# Test_board_gotta_be_quick.net
KiCad netlist of a schematic drawn in Altium Designer
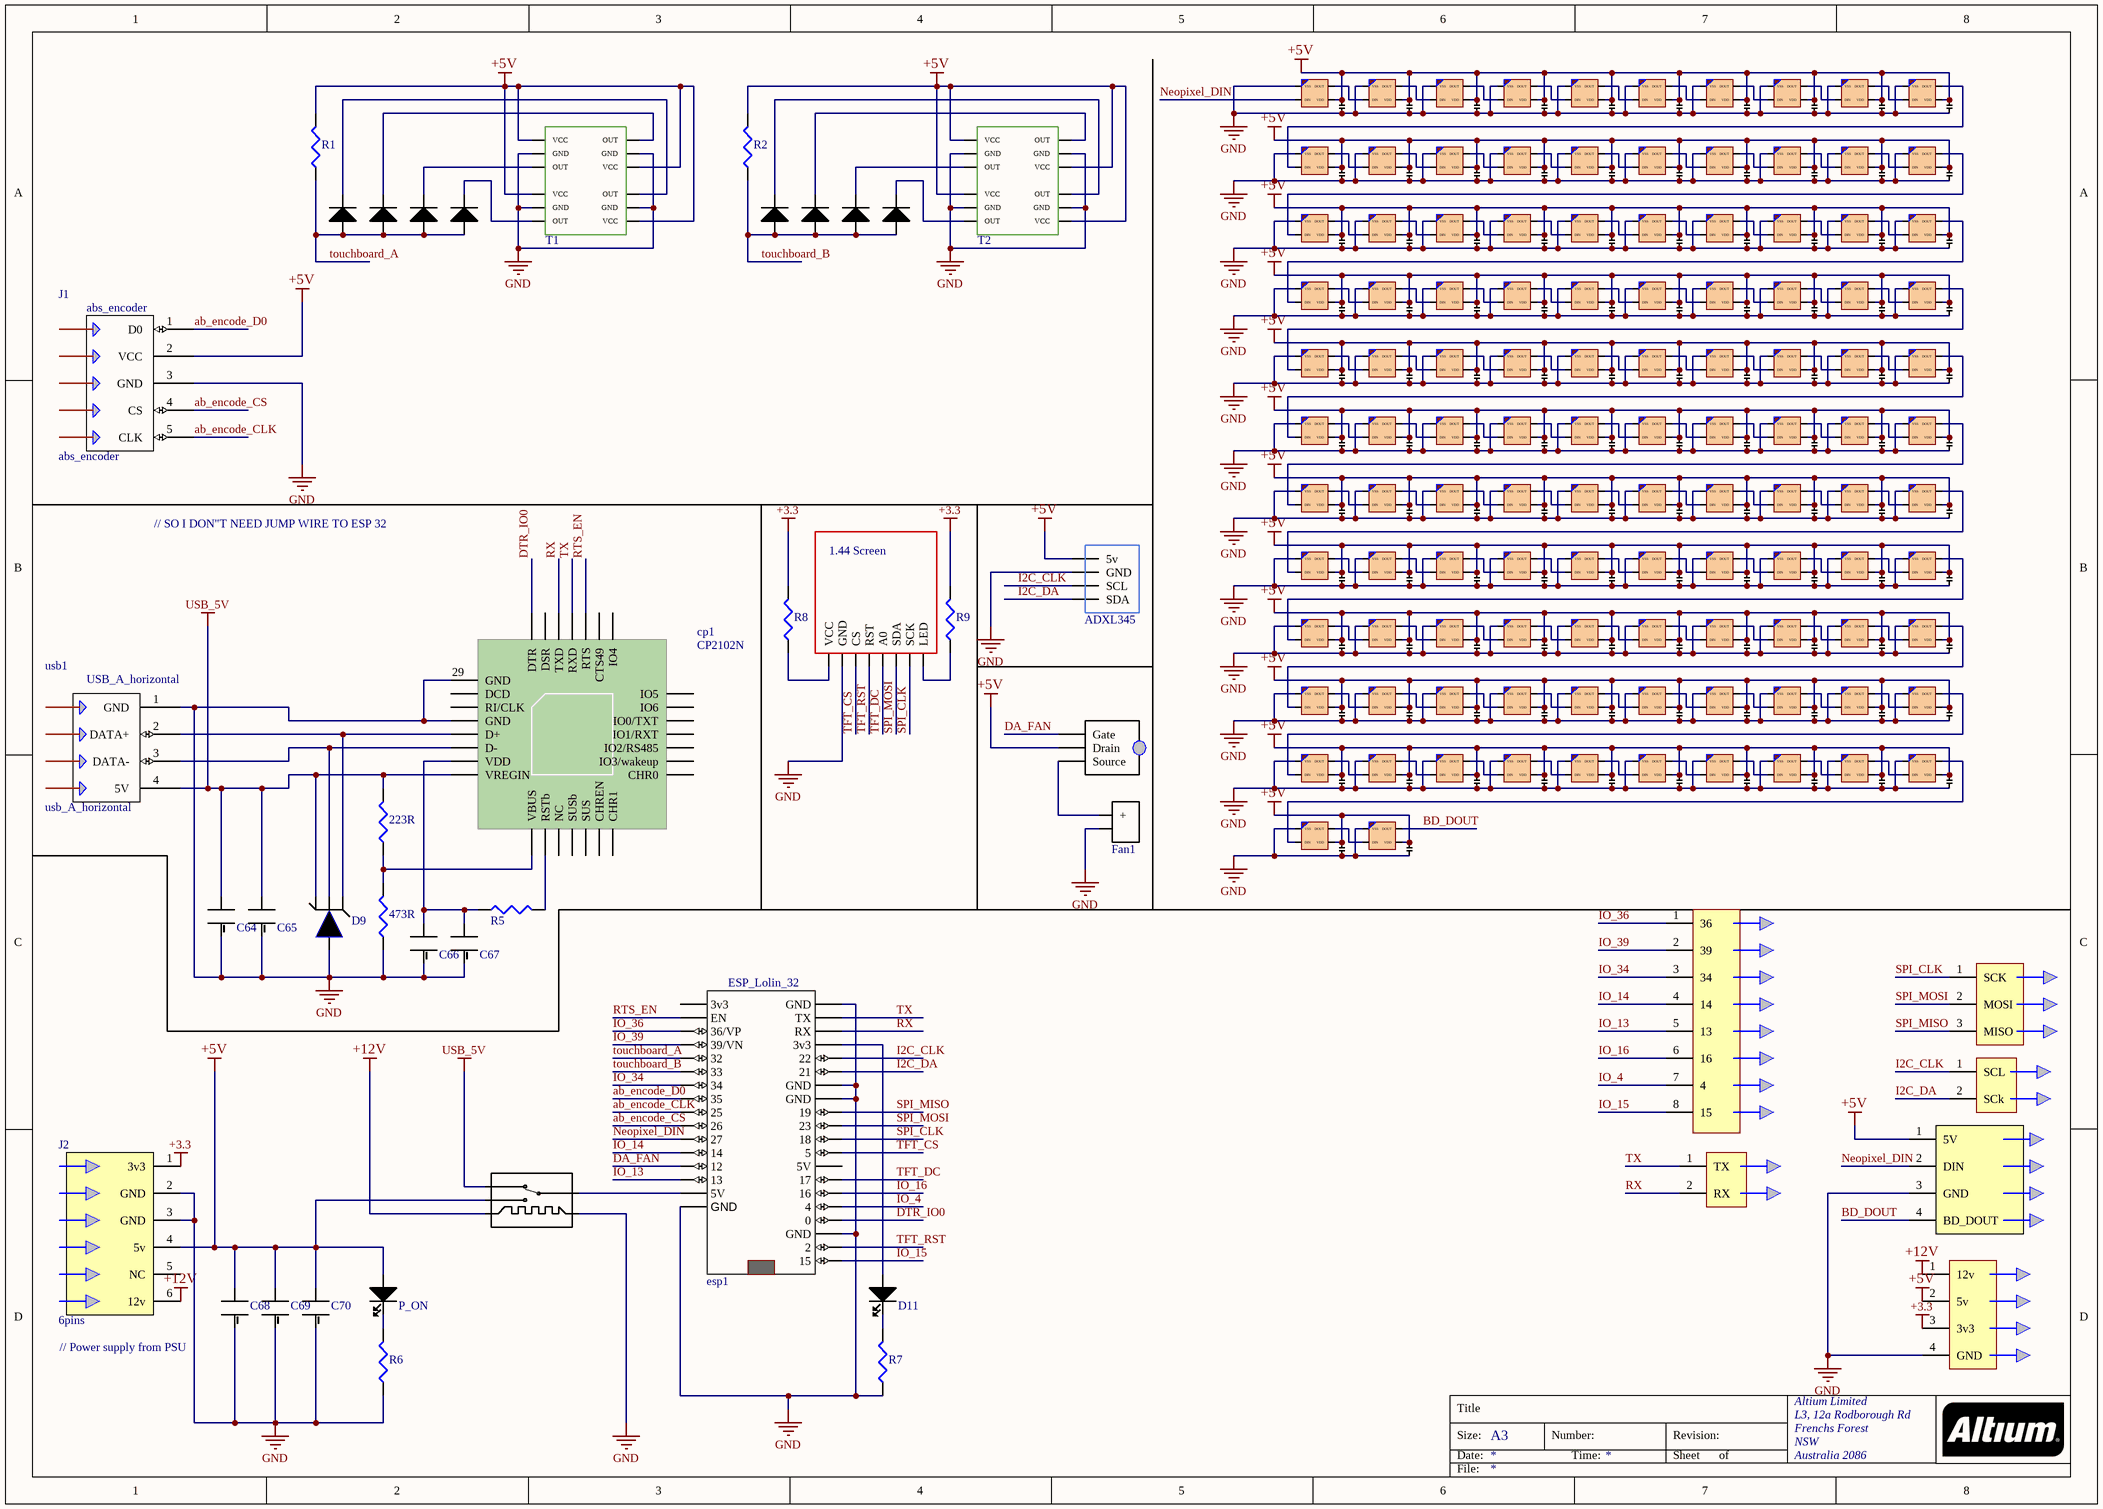
[diagram p0: Test_board_gotta_be_quick.SchDoc]

(export (version "E")
  (design (tool "Eeschema 10.0.6"))
  (components
    (comp (ref "223R")
      (value "22.1k")
      (footprint "R0805")
      (description "Res Thick Film 0805 360 Ohm 1% 0.125W(1/8W) ±100ppm/C Molded SMD Automotive Paper T/R")
      (fields (field (name "TOLERANCE") "1%"))
      (libsource (lib "WTFschlibra") (part "resistor(CRCW0805360RFKEA"))
    )
    (comp (ref "473R")
      (value "47.5k")
      (footprint "R0805")
      (description "Res Thick Film 0805 360 Ohm 1% 0.125W(1/8W) ±100ppm/C Molded SMD Automotive Paper T/R")
      (fields (field (name "TOLERANCE") "1%"))
      (libsource (lib "WTFschlibra") (part "resistor(CRCW0805360RFKEA"))
    )
    (comp (ref "ADXL345")
      (value "ADXL345")
      (footprint "ADXL345")
      (libsource (lib "WTFschlibra") (part "ADXL345"))
    )
    (comp (ref "C1")
      (value "capacitor0.1uf")
      (footprint "Capacitor0805")
      (description "for leds and smol")
      (libsource (lib "WTFschlibra") (part "capacitor0.1uf"))
    )
    (comp (ref "C2")
      (value "capacitor0.1uf")
      (footprint "Capacitor0805")
      (description "for leds and smol")
      (libsource (lib "WTFschlibra") (part "capacitor0.1uf"))
    )
    (comp (ref "C3")
      (value "capacitor0.1uf")
      (footprint "Capacitor0805")
      (description "for leds and smol")
      (libsource (lib "WTFschlibra") (part "capacitor0.1uf"))
    )
    (comp (ref "C4")
      (value "capacitor0.1uf")
      (footprint "Capacitor0805")
      (description "for leds and smol")
      (libsource (lib "WTFschlibra") (part "capacitor0.1uf"))
    )
    (comp (ref "C5")
      (value "capacitor0.1uf")
      (footprint "Capacitor0805")
      (description "for leds and smol")
      (libsource (lib "WTFschlibra") (part "capacitor0.1uf"))
    )
    (comp (ref "C6")
      (value "capacitor0.1uf")
      (footprint "Capacitor0805")
      (description "for leds and smol")
      (libsource (lib "WTFschlibra") (part "capacitor0.1uf"))
    )
    (comp (ref "C7")
      (value "capacitor0.1uf")
      (footprint "Capacitor0805")
      (description "for leds and smol")
      (libsource (lib "WTFschlibra") (part "capacitor0.1uf"))
    )
    (comp (ref "C8")
      (value "capacitor0.1uf")
      (footprint "Capacitor0805")
      (description "for leds and smol")
      (libsource (lib "WTFschlibra") (part "capacitor0.1uf"))
    )
    (comp (ref "C9")
      (value "capacitor0.1uf")
      (footprint "Capacitor0805")
      (description "for leds and smol")
      (libsource (lib "WTFschlibra") (part "capacitor0.1uf"))
    )
    (comp (ref "C10")
      (value "capacitor0.1uf")
      (footprint "Capacitor0805")
      (description "for leds and smol")
      (libsource (lib "WTFschlibra") (part "capacitor0.1uf"))
    )
    (comp (ref "C11")
      (value "capacitor0.1uf")
      (footprint "Capacitor0805")
      (description "for leds and smol")
      (libsource (lib "WTFschlibra") (part "capacitor0.1uf"))
    )
    (comp (ref "C12")
      (value "capacitor0.1uf")
      (footprint "Capacitor0805")
      (description "for leds and smol")
      (libsource (lib "WTFschlibra") (part "capacitor0.1uf"))
    )
    (comp (ref "C13")
      (value "capacitor0.1uf")
      (footprint "Capacitor0805")
      (description "for leds and smol")
      (libsource (lib "WTFschlibra") (part "capacitor0.1uf"))
    )
    (comp (ref "C14")
      (value "capacitor0.1uf")
      (footprint "Capacitor0805")
      (description "for leds and smol")
      (libsource (lib "WTFschlibra") (part "capacitor0.1uf"))
    )
    (comp (ref "C15")
      (value "capacitor0.1uf")
      (footprint "Capacitor0805")
      (description "for leds and smol")
      (libsource (lib "WTFschlibra") (part "capacitor0.1uf"))
    )
    (comp (ref "C16")
      (value "capacitor0.1uf")
      (footprint "Capacitor0805")
      (description "for leds and smol")
      (libsource (lib "WTFschlibra") (part "capacitor0.1uf"))
    )
    (comp (ref "C17")
      (value "capacitor0.1uf")
      (footprint "Capacitor0805")
      (description "for leds and smol")
      (libsource (lib "WTFschlibra") (part "capacitor0.1uf"))
    )
    (comp (ref "C18")
      (value "capacitor0.1uf")
      (footprint "Capacitor0805")
      (description "for leds and smol")
      (libsource (lib "WTFschlibra") (part "capacitor0.1uf"))
    )
    (comp (ref "C19")
      (value "capacitor0.1uf")
      (footprint "Capacitor0805")
      (description "for leds and smol")
      (libsource (lib "WTFschlibra") (part "capacitor0.1uf"))
    )
    (comp (ref "C20")
      (value "capacitor0.1uf")
      (footprint "Capacitor0805")
      (description "for leds and smol")
      (libsource (lib "WTFschlibra") (part "capacitor0.1uf"))
    )
    (comp (ref "C21")
      (value "capacitor0.1uf")
      (footprint "Capacitor0805")
      (description "for leds and smol")
      (libsource (lib "WTFschlibra") (part "capacitor0.1uf"))
    )
    (comp (ref "C22")
      (value "capacitor0.1uf")
      (footprint "Capacitor0805")
      (description "for leds and smol")
      (libsource (lib "WTFschlibra") (part "capacitor0.1uf"))
    )
    (comp (ref "C23")
      (value "capacitor0.1uf")
      (footprint "Capacitor0805")
      (description "for leds and smol")
      (libsource (lib "WTFschlibra") (part "capacitor0.1uf"))
    )
    (comp (ref "C24")
      (value "capacitor0.1uf")
      (footprint "Capacitor0805")
      (description "for leds and smol")
      (libsource (lib "WTFschlibra") (part "capacitor0.1uf"))
    )
    (comp (ref "C25")
      (value "capacitor0.1uf")
      (footprint "Capacitor0805")
      (description "for leds and smol")
      (libsource (lib "WTFschlibra") (part "capacitor0.1uf"))
    )
    (comp (ref "C26")
      (value "capacitor0.1uf")
      (footprint "Capacitor0805")
      (description "for leds and smol")
      (libsource (lib "WTFschlibra") (part "capacitor0.1uf"))
    )
    (comp (ref "C27")
      (value "capacitor0.1uf")
      (footprint "Capacitor0805")
      (description "for leds and smol")
      (libsource (lib "WTFschlibra") (part "capacitor0.1uf"))
    )
    (comp (ref "C28")
      (value "capacitor0.1uf")
      (footprint "Capacitor0805")
      (description "for leds and smol")
      (libsource (lib "WTFschlibra") (part "capacitor0.1uf"))
    )
    (comp (ref "C29")
      (value "capacitor0.1uf")
      (footprint "Capacitor0805")
      (description "for leds and smol")
      (libsource (lib "WTFschlibra") (part "capacitor0.1uf"))
    )
    (comp (ref "C30")
      (value "capacitor0.1uf")
      (footprint "Capacitor0805")
      (description "for leds and smol")
      (libsource (lib "WTFschlibra") (part "capacitor0.1uf"))
    )
    (comp (ref "C31")
      (value "capacitor0.1uf")
      (footprint "Capacitor0805")
      (description "for leds and smol")
      (libsource (lib "WTFschlibra") (part "capacitor0.1uf"))
    )
    (comp (ref "C32")
      (value "capacitor0.1uf")
      (footprint "Capacitor0805")
      (description "for leds and smol")
      (libsource (lib "WTFschlibra") (part "capacitor0.1uf"))
    )
    (comp (ref "C33")
      (value "capacitor0.1uf")
      (footprint "Capacitor0805")
      (description "for leds and smol")
      (libsource (lib "WTFschlibra") (part "capacitor0.1uf"))
    )
    (comp (ref "C34")
      (value "capacitor0.1uf")
      (footprint "Capacitor0805")
      (description "for leds and smol")
      (libsource (lib "WTFschlibra") (part "capacitor0.1uf"))
    )
    (comp (ref "C35")
      (value "capacitor0.1uf")
      (footprint "Capacitor0805")
      (description "for leds and smol")
      (libsource (lib "WTFschlibra") (part "capacitor0.1uf"))
    )
    (comp (ref "C36")
      (value "capacitor0.1uf")
      (footprint "Capacitor0805")
      (description "for leds and smol")
      (libsource (lib "WTFschlibra") (part "capacitor0.1uf"))
    )
    (comp (ref "C37")
      (value "capacitor0.1uf")
      (footprint "Capacitor0805")
      (description "for leds and smol")
      (libsource (lib "WTFschlibra") (part "capacitor0.1uf"))
    )
    (comp (ref "C38")
      (value "capacitor0.1uf")
      (footprint "Capacitor0805")
      (description "for leds and smol")
      (libsource (lib "WTFschlibra") (part "capacitor0.1uf"))
    )
    (comp (ref "C39")
      (value "capacitor0.1uf")
      (footprint "Capacitor0805")
      (description "for leds and smol")
      (libsource (lib "WTFschlibra") (part "capacitor0.1uf"))
    )
    (comp (ref "C40")
      (value "capacitor0.1uf")
      (footprint "Capacitor0805")
      (description "for leds and smol")
      (libsource (lib "WTFschlibra") (part "capacitor0.1uf"))
    )
    (comp (ref "C41")
      (value "capacitor0.1uf")
      (footprint "Capacitor0805")
      (description "for leds and smol")
      (libsource (lib "WTFschlibra") (part "capacitor0.1uf"))
    )
    (comp (ref "C42")
      (value "capacitor0.1uf")
      (footprint "Capacitor0805")
      (description "for leds and smol")
      (libsource (lib "WTFschlibra") (part "capacitor0.1uf"))
    )
    (comp (ref "C43")
      (value "capacitor0.1uf")
      (footprint "Capacitor0805")
      (description "for leds and smol")
      (libsource (lib "WTFschlibra") (part "capacitor0.1uf"))
    )
    (comp (ref "C44")
      (value "capacitor0.1uf")
      (footprint "Capacitor0805")
      (description "for leds and smol")
      (libsource (lib "WTFschlibra") (part "capacitor0.1uf"))
    )
    (comp (ref "C45")
      (value "capacitor0.1uf")
      (footprint "Capacitor0805")
      (description "for leds and smol")
      (libsource (lib "WTFschlibra") (part "capacitor0.1uf"))
    )
    (comp (ref "C46")
      (value "capacitor0.1uf")
      (footprint "Capacitor0805")
      (description "for leds and smol")
      (libsource (lib "WTFschlibra") (part "capacitor0.1uf"))
    )
    (comp (ref "C47")
      (value "capacitor0.1uf")
      (footprint "Capacitor0805")
      (description "for leds and smol")
      (libsource (lib "WTFschlibra") (part "capacitor0.1uf"))
    )
    (comp (ref "C48")
      (value "capacitor0.1uf")
      (footprint "Capacitor0805")
      (description "for leds and smol")
      (libsource (lib "WTFschlibra") (part "capacitor0.1uf"))
    )
    (comp (ref "C49")
      (value "capacitor0.1uf")
      (footprint "Capacitor0805")
      (description "for leds and smol")
      (libsource (lib "WTFschlibra") (part "capacitor0.1uf"))
    )
    (comp (ref "C50")
      (value "capacitor0.1uf")
      (footprint "Capacitor0805")
      (description "for leds and smol")
      (libsource (lib "WTFschlibra") (part "capacitor0.1uf"))
    )
    (comp (ref "C51")
      (value "capacitor0.1uf")
      (footprint "Capacitor0805")
      (description "for leds and smol")
      (libsource (lib "WTFschlibra") (part "capacitor0.1uf"))
    )
    (comp (ref "C52")
      (value "capacitor0.1uf")
      (footprint "Capacitor0805")
      (description "for leds and smol")
      (libsource (lib "WTFschlibra") (part "capacitor0.1uf"))
    )
    (comp (ref "C53")
      (value "capacitor0.1uf")
      (footprint "Capacitor0805")
      (description "for leds and smol")
      (libsource (lib "WTFschlibra") (part "capacitor0.1uf"))
    )
    (comp (ref "C54")
      (value "capacitor0.1uf")
      (footprint "Capacitor0805")
      (description "for leds and smol")
      (libsource (lib "WTFschlibra") (part "capacitor0.1uf"))
    )
    (comp (ref "C55")
      (value "capacitor0.1uf")
      (footprint "Capacitor0805")
      (description "for leds and smol")
      (libsource (lib "WTFschlibra") (part "capacitor0.1uf"))
    )
    (comp (ref "C56")
      (value "capacitor0.1uf")
      (footprint "Capacitor0805")
      (description "for leds and smol")
      (libsource (lib "WTFschlibra") (part "capacitor0.1uf"))
    )
    (comp (ref "C57")
      (value "capacitor0.1uf")
      (footprint "Capacitor0805")
      (description "for leds and smol")
      (libsource (lib "WTFschlibra") (part "capacitor0.1uf"))
    )
    (comp (ref "C58")
      (value "capacitor0.1uf")
      (footprint "Capacitor0805")
      (description "for leds and smol")
      (libsource (lib "WTFschlibra") (part "capacitor0.1uf"))
    )
    (comp (ref "C59")
      (value "capacitor0.1uf")
      (footprint "Capacitor0805")
      (description "for leds and smol")
      (libsource (lib "WTFschlibra") (part "capacitor0.1uf"))
    )
    (comp (ref "C60")
      (value "capacitor0.1uf")
      (footprint "Capacitor0805")
      (description "for leds and smol")
      (libsource (lib "WTFschlibra") (part "capacitor0.1uf"))
    )
    (comp (ref "C61")
      (value "capacitor0.1uf")
      (footprint "Capacitor0805")
      (description "for leds and smol")
      (libsource (lib "WTFschlibra") (part "capacitor0.1uf"))
    )
    (comp (ref "C62")
      (value "capacitor0.1uf")
      (footprint "Capacitor0805")
      (description "for leds and smol")
      (libsource (lib "WTFschlibra") (part "capacitor0.1uf"))
    )
    (comp (ref "C63")
      (value "capacitor0.1uf")
      (footprint "Capacitor0805")
      (description "for leds and smol")
      (libsource (lib "WTFschlibra") (part "capacitor0.1uf"))
    )
    (comp (ref "C64")
      (value "4R7")
      (footprint "Capacitor0603")
      (description "Cap Ceramic 4.7uF 6.3V X5R 20% Pad SMD 0402 85C T/R")
      (fields (field (name "TOLERANCE") "20%"))
      (libsource (lib "WTFschlibra") (part "capacitor0603"))
    )
    (comp (ref "C65")
      (value "104")
      (footprint "Capacitor0603")
      (description "0.1uf")
      (fields (field (name "TOLERANCE") "20%"))
      (libsource (lib "WTFschlibra") (part "capacitor0603"))
    )
    (comp (ref "C66")
      (value "104")
      (footprint "Capacitor0603")
      (description "4.7")
      (fields (field (name "TOLERANCE") "20%"))
      (libsource (lib "WTFschlibra") (part "capacitor0603"))
    )
    (comp (ref "C67")
      (value "4R7")
      (footprint "Capacitor0603")
      (description "0.1")
      (fields (field (name "TOLERANCE") "20%"))
      (libsource (lib "WTFschlibra") (part "capacitor0603"))
    )
    (comp (ref "C68")
      (value "EEU-FM0J331")
      (footprint "2.5mmCapacitor")
      (description "Cap 330 uF;  Tol 20%;  Vol-Rtg 6.3 VDC;  Radial;  6.3x11.2;  Bulk")
      (fields (field (name "TOLERANCE") "20%") (field (name "VOLTAGE") "6.3V"))
      (libsource (lib "WTFschlibra") (part "EEU-FM0J331"))
    )
    (comp (ref "C69")
      (value "EEU-FM0J331")
      (footprint "2.5mmCapacitor")
      (description "Cap 330 uF;  Tol 20%;  Vol-Rtg 6.3 VDC;  Radial;  6.3x11.2;  Bulk")
      (fields (field (name "TOLERANCE") "20%") (field (name "VOLTAGE") "6.3V"))
      (libsource (lib "WTFschlibra") (part "EEU-FM0J331"))
    )
    (comp (ref "C70")
      (value "EEU-FM0J331")
      (footprint "2.5mmCapacitor")
      (description "Cap 330 uF;  Tol 20%;  Vol-Rtg 6.3 VDC;  Radial;  6.3x11.2;  Bulk")
      (fields (field (name "TOLERANCE") "20%") (field (name "VOLTAGE") "6.3V"))
      (libsource (lib "WTFschlibra") (part "EEU-FM0J331"))
    )
    (comp (ref "C71")
      (value "capacitor0.1uf")
      (footprint "Capacitor0805")
      (description "for leds and smol")
      (libsource (lib "WTFschlibra") (part "capacitor0.1uf"))
    )
    (comp (ref "C72")
      (value "capacitor0.1uf")
      (footprint "Capacitor0805")
      (description "for leds and smol")
      (libsource (lib "WTFschlibra") (part "capacitor0.1uf"))
    )
    (comp (ref "C73")
      (value "capacitor0.1uf")
      (footprint "Capacitor0805")
      (description "for leds and smol")
      (libsource (lib "WTFschlibra") (part "capacitor0.1uf"))
    )
    (comp (ref "C74")
      (value "capacitor0.1uf")
      (footprint "Capacitor0805")
      (description "for leds and smol")
      (libsource (lib "WTFschlibra") (part "capacitor0.1uf"))
    )
    (comp (ref "C75")
      (value "capacitor0.1uf")
      (footprint "Capacitor0805")
      (description "for leds and smol")
      (libsource (lib "WTFschlibra") (part "capacitor0.1uf"))
    )
    (comp (ref "C76")
      (value "capacitor0.1uf")
      (footprint "Capacitor0805")
      (description "for leds and smol")
      (libsource (lib "WTFschlibra") (part "capacitor0.1uf"))
    )
    (comp (ref "C77")
      (value "capacitor0.1uf")
      (footprint "Capacitor0805")
      (description "for leds and smol")
      (libsource (lib "WTFschlibra") (part "capacitor0.1uf"))
    )
    (comp (ref "C78")
      (value "capacitor0.1uf")
      (footprint "Capacitor0805")
      (description "for leds and smol")
      (libsource (lib "WTFschlibra") (part "capacitor0.1uf"))
    )
    (comp (ref "C79")
      (value "capacitor0.1uf")
      (footprint "Capacitor0805")
      (description "for leds and smol")
      (libsource (lib "WTFschlibra") (part "capacitor0.1uf"))
    )
    (comp (ref "C80")
      (value "capacitor0.1uf")
      (footprint "Capacitor0805")
      (description "for leds and smol")
      (libsource (lib "WTFschlibra") (part "capacitor0.1uf"))
    )
    (comp (ref "C81")
      (value "capacitor0.1uf")
      (footprint "Capacitor0805")
      (description "for leds and smol")
      (libsource (lib "WTFschlibra") (part "capacitor0.1uf"))
    )
    (comp (ref "C82")
      (value "capacitor0.1uf")
      (footprint "Capacitor0805")
      (description "for leds and smol")
      (libsource (lib "WTFschlibra") (part "capacitor0.1uf"))
    )
    (comp (ref "C83")
      (value "capacitor0.1uf")
      (footprint "Capacitor0805")
      (description "for leds and smol")
      (libsource (lib "WTFschlibra") (part "capacitor0.1uf"))
    )
    (comp (ref "C84")
      (value "capacitor0.1uf")
      (footprint "Capacitor0805")
      (description "for leds and smol")
      (libsource (lib "WTFschlibra") (part "capacitor0.1uf"))
    )
    (comp (ref "C85")
      (value "capacitor0.1uf")
      (footprint "Capacitor0805")
      (description "for leds and smol")
      (libsource (lib "WTFschlibra") (part "capacitor0.1uf"))
    )
    (comp (ref "C86")
      (value "capacitor0.1uf")
      (footprint "Capacitor0805")
      (description "for leds and smol")
      (libsource (lib "WTFschlibra") (part "capacitor0.1uf"))
    )
    (comp (ref "C87")
      (value "capacitor0.1uf")
      (footprint "Capacitor0805")
      (description "for leds and smol")
      (libsource (lib "WTFschlibra") (part "capacitor0.1uf"))
    )
    (comp (ref "C88")
      (value "capacitor0.1uf")
      (footprint "Capacitor0805")
      (description "for leds and smol")
      (libsource (lib "WTFschlibra") (part "capacitor0.1uf"))
    )
    (comp (ref "C89")
      (value "capacitor0.1uf")
      (footprint "Capacitor0805")
      (description "for leds and smol")
      (libsource (lib "WTFschlibra") (part "capacitor0.1uf"))
    )
    (comp (ref "C90")
      (value "capacitor0.1uf")
      (footprint "Capacitor0805")
      (description "for leds and smol")
      (libsource (lib "WTFschlibra") (part "capacitor0.1uf"))
    )
    (comp (ref "C91")
      (value "capacitor0.1uf")
      (footprint "Capacitor0805")
      (description "for leds and smol")
      (libsource (lib "WTFschlibra") (part "capacitor0.1uf"))
    )
    (comp (ref "C92")
      (value "capacitor0.1uf")
      (footprint "Capacitor0805")
      (description "for leds and smol")
      (libsource (lib "WTFschlibra") (part "capacitor0.1uf"))
    )
    (comp (ref "C93")
      (value "capacitor0.1uf")
      (footprint "Capacitor0805")
      (description "for leds and smol")
      (libsource (lib "WTFschlibra") (part "capacitor0.1uf"))
    )
    (comp (ref "C94")
      (value "capacitor0.1uf")
      (footprint "Capacitor0805")
      (description "for leds and smol")
      (libsource (lib "WTFschlibra") (part "capacitor0.1uf"))
    )
    (comp (ref "C95")
      (value "capacitor0.1uf")
      (footprint "Capacitor0805")
      (description "for leds and smol")
      (libsource (lib "WTFschlibra") (part "capacitor0.1uf"))
    )
    (comp (ref "C96")
      (value "capacitor0.1uf")
      (footprint "Capacitor0805")
      (description "for leds and smol")
      (libsource (lib "WTFschlibra") (part "capacitor0.1uf"))
    )
    (comp (ref "C97")
      (value "capacitor0.1uf")
      (footprint "Capacitor0805")
      (description "for leds and smol")
      (libsource (lib "WTFschlibra") (part "capacitor0.1uf"))
    )
    (comp (ref "C98")
      (value "capacitor0.1uf")
      (footprint "Capacitor0805")
      (description "for leds and smol")
      (libsource (lib "WTFschlibra") (part "capacitor0.1uf"))
    )
    (comp (ref "C99")
      (value "capacitor0.1uf")
      (footprint "Capacitor0805")
      (description "for leds and smol")
      (libsource (lib "WTFschlibra") (part "capacitor0.1uf"))
    )
    (comp (ref "C100")
      (value "capacitor0.1uf")
      (footprint "Capacitor0805")
      (description "for leds and smol")
      (libsource (lib "WTFschlibra") (part "capacitor0.1uf"))
    )
    (comp (ref "C101")
      (value "capacitor0.1uf")
      (footprint "Capacitor0805")
      (description "for leds and smol")
      (libsource (lib "WTFschlibra") (part "capacitor0.1uf"))
    )
    (comp (ref "C102")
      (value "capacitor0.1uf")
      (footprint "Capacitor0805")
      (description "for leds and smol")
      (libsource (lib "WTFschlibra") (part "capacitor0.1uf"))
    )
    (comp (ref "C103")
      (value "capacitor0.1uf")
      (footprint "Capacitor0805")
      (description "for leds and smol")
      (libsource (lib "WTFschlibra") (part "capacitor0.1uf"))
    )
    (comp (ref "C104")
      (value "capacitor0.1uf")
      (footprint "Capacitor0805")
      (description "for leds and smol")
      (libsource (lib "WTFschlibra") (part "capacitor0.1uf"))
    )
    (comp (ref "C105")
      (value "capacitor0.1uf")
      (footprint "Capacitor0805")
      (description "for leds and smol")
      (libsource (lib "WTFschlibra") (part "capacitor0.1uf"))
    )
    (comp (ref "C106")
      (value "capacitor0.1uf")
      (footprint "Capacitor0805")
      (description "for leds and smol")
      (libsource (lib "WTFschlibra") (part "capacitor0.1uf"))
    )
    (comp (ref "C107")
      (value "capacitor0.1uf")
      (footprint "Capacitor0805")
      (description "for leds and smol")
      (libsource (lib "WTFschlibra") (part "capacitor0.1uf"))
    )
    (comp (ref "C108")
      (value "capacitor0.1uf")
      (footprint "Capacitor0805")
      (description "for leds and smol")
      (libsource (lib "WTFschlibra") (part "capacitor0.1uf"))
    )
    (comp (ref "C109")
      (value "capacitor0.1uf")
      (footprint "Capacitor0805")
      (description "for leds and smol")
      (libsource (lib "WTFschlibra") (part "capacitor0.1uf"))
    )
    (comp (ref "C110")
      (value "capacitor0.1uf")
      (footprint "Capacitor0805")
      (description "for leds and smol")
      (libsource (lib "WTFschlibra") (part "capacitor0.1uf"))
    )
    (comp (ref "C111")
      (value "capacitor0.1uf")
      (footprint "Capacitor0805")
      (description "for leds and smol")
      (libsource (lib "WTFschlibra") (part "capacitor0.1uf"))
    )
    (comp (ref "C112")
      (value "capacitor0.1uf")
      (footprint "Capacitor0805")
      (description "for leds and smol")
      (libsource (lib "WTFschlibra") (part "capacitor0.1uf"))
    )
    (comp (ref "C113")
      (value "capacitor0.1uf")
      (footprint "Capacitor0805")
      (description "for leds and smol")
      (libsource (lib "WTFschlibra") (part "capacitor0.1uf"))
    )
    (comp (ref "C114")
      (value "capacitor0.1uf")
      (footprint "Capacitor0805")
      (description "for leds and smol")
      (libsource (lib "WTFschlibra") (part "capacitor0.1uf"))
    )
    (comp (ref "C115")
      (value "capacitor0.1uf")
      (footprint "Capacitor0805")
      (description "for leds and smol")
      (libsource (lib "WTFschlibra") (part "capacitor0.1uf"))
    )
    (comp (ref "C116")
      (value "capacitor0.1uf")
      (footprint "Capacitor0805")
      (description "for leds and smol")
      (libsource (lib "WTFschlibra") (part "capacitor0.1uf"))
    )
    (comp (ref "C117")
      (value "capacitor0.1uf")
      (footprint "Capacitor0805")
      (description "for leds and smol")
      (libsource (lib "WTFschlibra") (part "capacitor0.1uf"))
    )
    (comp (ref "C118")
      (value "capacitor0.1uf")
      (footprint "Capacitor0805")
      (description "for leds and smol")
      (libsource (lib "WTFschlibra") (part "capacitor0.1uf"))
    )
    (comp (ref "C119")
      (value "capacitor0.1uf")
      (footprint "Capacitor0805")
      (description "for leds and smol")
      (libsource (lib "WTFschlibra") (part "capacitor0.1uf"))
    )
    (comp (ref "cp1")
      (value "CP2102N")
      (footprint "CP2102N_QFN28")
      (description "Full Speed USB to UART Bridge USB 2.0 3.3V T/R Automotive 28-Pin QFN EP")
      (libsource (lib "WTFschlibra") (part "CP2102N-A02-GQFN28R"))
    )
    (comp (ref "D1")
      (value "LL4148")
      (footprint "SOD80-LL4148")
      (description "ON SEMICONDUCTOR - LL4148 - Small Signal Diode, Single, 100 V, 200 mA, 1 V, 4 ns, 2 A")
      (fields (field (name "VOLTAGE") "100V"))
      (libsource (lib "WTFschlibra") (part "LL4148"))
    )
    (comp (ref "D2")
      (value "LL4148")
      (footprint "SOD80-LL4148")
      (description "ON SEMICONDUCTOR - LL4148 - Small Signal Diode, Single, 100 V, 200 mA, 1 V, 4 ns, 2 A")
      (fields (field (name "VOLTAGE") "100V"))
      (libsource (lib "WTFschlibra") (part "LL4148"))
    )
    (comp (ref "D3")
      (value "LL4148")
      (footprint "SOD80-LL4148")
      (description "ON SEMICONDUCTOR - LL4148 - Small Signal Diode, Single, 100 V, 200 mA, 1 V, 4 ns, 2 A")
      (fields (field (name "VOLTAGE") "100V"))
      (libsource (lib "WTFschlibra") (part "LL4148"))
    )
    (comp (ref "D4")
      (value "LL4148")
      (footprint "SOD80-LL4148")
      (description "ON SEMICONDUCTOR - LL4148 - Small Signal Diode, Single, 100 V, 200 mA, 1 V, 4 ns, 2 A")
      (fields (field (name "VOLTAGE") "100V"))
      (libsource (lib "WTFschlibra") (part "LL4148"))
    )
    (comp (ref "D5")
      (value "LL4148")
      (footprint "SOD80-LL4148")
      (description "ON SEMICONDUCTOR - LL4148 - Small Signal Diode, Single, 100 V, 200 mA, 1 V, 4 ns, 2 A")
      (fields (field (name "VOLTAGE") "100V"))
      (libsource (lib "WTFschlibra") (part "LL4148"))
    )
    (comp (ref "D6")
      (value "LL4148")
      (footprint "SOD80-LL4148")
      (description "ON SEMICONDUCTOR - LL4148 - Small Signal Diode, Single, 100 V, 200 mA, 1 V, 4 ns, 2 A")
      (fields (field (name "VOLTAGE") "100V"))
      (libsource (lib "WTFschlibra") (part "LL4148"))
    )
    (comp (ref "D7")
      (value "LL4148")
      (footprint "SOD80-LL4148")
      (description "ON SEMICONDUCTOR - LL4148 - Small Signal Diode, Single, 100 V, 200 mA, 1 V, 4 ns, 2 A")
      (fields (field (name "VOLTAGE") "100V"))
      (libsource (lib "WTFschlibra") (part "LL4148"))
    )
    (comp (ref "D8")
      (value "LL4148")
      (footprint "SOD80-LL4148")
      (description "ON SEMICONDUCTOR - LL4148 - Small Signal Diode, Single, 100 V, 200 mA, 1 V, 4 ns, 2 A")
      (fields (field (name "VOLTAGE") "100V"))
      (libsource (lib "WTFschlibra") (part "LL4148"))
    )
    (comp (ref "D9")
      (value "SP0503BAHTG")
      (footprint "SP0503BAHTG - SOT143-4")
      (description "ESD Suppressor TVS 5.5V 4-Pin(3+Tab) SOT-143 T/R")
      (libsource (lib "WTFschlibra") (part "SP0503BAHTG"))
    )
    (comp (ref "D11")
      (value "esp_on")
      (footprint "LED0603")
      (description "LED BLUE CLEAR CHIP SMD")
      (libsource (lib "WTFschlibra") (part "LTST-C190TBKT"))
    )
    (comp (ref "esp1")
      (value "processor")
      (footprint "ESP_32_socket")
      (libsource (lib "WTFschlibra") (part "ESP_32_lolin"))
    )
    (comp (ref "Fan1")
      (value "5vFanPin")
      (footprint "1x2 dupont")
      (libsource (lib "WTFschlibra") (part "5vFanPin"))
    )
    (comp (ref "irl") (value "IRL3713") (footprint "TO_220") (libsource (lib "WTFschlibra") (part "IRL3713")))
    (comp (ref "J1")
      (value "abs_encoder")
      (footprint "xh 2.54 5 pin")
      (libsource (lib "WTFschlibra") (part "Abs_encoder_pins"))
    )
    (comp (ref "J2")
      (value "6pins")
      (footprint "4.2mm 6pin power connector")
      (description "MiniFit Jr RA Hdr Assy LCP 6 w/press pgs")
      (libsource (lib "WTFschlibra") (part "4.2mm 6pin module connector"))
    )
    (comp (ref "J3")
      (value "ws2812")
      (footprint "1x4 DUPONT")
      (description "for neopixels array")
      (libsource (lib "WTFschlibra") (part "4.2mm 4pin 39300040"))
    )
    (comp (ref "J4")
      (value "SPI")
      (footprint "1x3 DUPONT")
      (libsource (lib "WTFschlibra") (part "1x3 dupont SPI"))
    )
    (comp (ref "J5")
      (value "I2C")
      (footprint "1x2 dupont")
      (libsource (lib "WTFschlibra") (part "1x2 dupont I2C"))
    )
    (comp (ref "J6")
      (value "1x8 dupont io pins")
      (footprint "1x8 dupont")
      (libsource (lib "WTFschlibra") (part "1x8 dupont io pins"))
    )
    (comp (ref "J7")
      (value "1x4 dupont power")
      (footprint "1x4 DUPONT")
      (libsource (lib "WTFschlibra") (part "1x4 dupont power"))
    )
    (comp (ref "J8")
      (value "TX")
      (footprint "1x2 dupont")
      (libsource (lib "WTFschlibra") (part "1x2 dupont TXRX"))
    )
    (comp (ref "LED1")
      (value "Ws2812B")
      (footprint "ws2812b")
      (libsource (lib "WTFschlibra") (part "Ws2812B"))
    )
    (comp (ref "LED2")
      (value "Ws2812B")
      (footprint "ws2812b")
      (libsource (lib "WTFschlibra") (part "Ws2812B"))
    )
    (comp (ref "LED3")
      (value "Ws2812B")
      (footprint "ws2812b")
      (libsource (lib "WTFschlibra") (part "Ws2812B"))
    )
    (comp (ref "LED4")
      (value "Ws2812B")
      (footprint "ws2812b")
      (libsource (lib "WTFschlibra") (part "Ws2812B"))
    )
    (comp (ref "LED5")
      (value "Ws2812B")
      (footprint "ws2812b")
      (libsource (lib "WTFschlibra") (part "Ws2812B"))
    )
    (comp (ref "LED6")
      (value "Ws2812B")
      (footprint "ws2812b")
      (libsource (lib "WTFschlibra") (part "Ws2812B"))
    )
    (comp (ref "LED7")
      (value "Ws2812B")
      (footprint "ws2812b")
      (libsource (lib "WTFschlibra") (part "Ws2812B"))
    )
    (comp (ref "LED8")
      (value "Ws2812B")
      (footprint "ws2812b")
      (libsource (lib "WTFschlibra") (part "Ws2812B"))
    )
    (comp (ref "LED9")
      (value "Ws2812B")
      (footprint "ws2812b")
      (libsource (lib "WTFschlibra") (part "Ws2812B"))
    )
    (comp (ref "LED10")
      (value "Ws2812B")
      (footprint "ws2812b")
      (libsource (lib "WTFschlibra") (part "Ws2812B"))
    )
    (comp (ref "LED11")
      (value "Ws2812B")
      (footprint "ws2812b")
      (libsource (lib "WTFschlibra") (part "Ws2812B"))
    )
    (comp (ref "LED12")
      (value "Ws2812B")
      (footprint "ws2812b")
      (libsource (lib "WTFschlibra") (part "Ws2812B"))
    )
    (comp (ref "LED13")
      (value "Ws2812B")
      (footprint "ws2812b")
      (libsource (lib "WTFschlibra") (part "Ws2812B"))
    )
    (comp (ref "LED14")
      (value "Ws2812B")
      (footprint "ws2812b")
      (libsource (lib "WTFschlibra") (part "Ws2812B"))
    )
    (comp (ref "LED15")
      (value "Ws2812B")
      (footprint "ws2812b")
      (libsource (lib "WTFschlibra") (part "Ws2812B"))
    )
    (comp (ref "LED16")
      (value "Ws2812B")
      (footprint "ws2812b")
      (libsource (lib "WTFschlibra") (part "Ws2812B"))
    )
    (comp (ref "LED17")
      (value "Ws2812B")
      (footprint "ws2812b")
      (libsource (lib "WTFschlibra") (part "Ws2812B"))
    )
    (comp (ref "LED18")
      (value "Ws2812B")
      (footprint "ws2812b")
      (libsource (lib "WTFschlibra") (part "Ws2812B"))
    )
    (comp (ref "LED19")
      (value "Ws2812B")
      (footprint "ws2812b")
      (libsource (lib "WTFschlibra") (part "Ws2812B"))
    )
    (comp (ref "LED20")
      (value "Ws2812B")
      (footprint "ws2812b")
      (libsource (lib "WTFschlibra") (part "Ws2812B"))
    )
    (comp (ref "LED21")
      (value "Ws2812B")
      (footprint "ws2812b")
      (libsource (lib "WTFschlibra") (part "Ws2812B"))
    )
    (comp (ref "LED22")
      (value "Ws2812B")
      (footprint "ws2812b")
      (libsource (lib "WTFschlibra") (part "Ws2812B"))
    )
    (comp (ref "LED23")
      (value "Ws2812B")
      (footprint "ws2812b")
      (libsource (lib "WTFschlibra") (part "Ws2812B"))
    )
    (comp (ref "LED24")
      (value "Ws2812B")
      (footprint "ws2812b")
      (libsource (lib "WTFschlibra") (part "Ws2812B"))
    )
    (comp (ref "LED25")
      (value "Ws2812B")
      (footprint "ws2812b")
      (libsource (lib "WTFschlibra") (part "Ws2812B"))
    )
    (comp (ref "LED26")
      (value "Ws2812B")
      (footprint "ws2812b")
      (libsource (lib "WTFschlibra") (part "Ws2812B"))
    )
    (comp (ref "LED27")
      (value "Ws2812B")
      (footprint "ws2812b")
      (libsource (lib "WTFschlibra") (part "Ws2812B"))
    )
    (comp (ref "LED28")
      (value "Ws2812B")
      (footprint "ws2812b")
      (libsource (lib "WTFschlibra") (part "Ws2812B"))
    )
    (comp (ref "LED29")
      (value "Ws2812B")
      (footprint "ws2812b")
      (libsource (lib "WTFschlibra") (part "Ws2812B"))
    )
    (comp (ref "LED30")
      (value "Ws2812B")
      (footprint "ws2812b")
      (libsource (lib "WTFschlibra") (part "Ws2812B"))
    )
    (comp (ref "LED31")
      (value "Ws2812B")
      (footprint "ws2812b")
      (libsource (lib "WTFschlibra") (part "Ws2812B"))
    )
    (comp (ref "LED32")
      (value "Ws2812B")
      (footprint "ws2812b")
      (libsource (lib "WTFschlibra") (part "Ws2812B"))
    )
    (comp (ref "LED33")
      (value "Ws2812B")
      (footprint "ws2812b")
      (libsource (lib "WTFschlibra") (part "Ws2812B"))
    )
    (comp (ref "LED34")
      (value "Ws2812B")
      (footprint "ws2812b")
      (libsource (lib "WTFschlibra") (part "Ws2812B"))
    )
    (comp (ref "LED35")
      (value "Ws2812B")
      (footprint "ws2812b")
      (libsource (lib "WTFschlibra") (part "Ws2812B"))
    )
    (comp (ref "LED36")
      (value "Ws2812B")
      (footprint "ws2812b")
      (libsource (lib "WTFschlibra") (part "Ws2812B"))
    )
    (comp (ref "LED37")
      (value "Ws2812B")
      (footprint "ws2812b")
      (libsource (lib "WTFschlibra") (part "Ws2812B"))
    )
    (comp (ref "LED38")
      (value "Ws2812B")
      (footprint "ws2812b")
      (libsource (lib "WTFschlibra") (part "Ws2812B"))
    )
    (comp (ref "LED39")
      (value "Ws2812B")
      (footprint "ws2812b")
      (libsource (lib "WTFschlibra") (part "Ws2812B"))
    )
    (comp (ref "LED40")
      (value "Ws2812B")
      (footprint "ws2812b")
      (libsource (lib "WTFschlibra") (part "Ws2812B"))
    )
    (comp (ref "LED41")
      (value "Ws2812B")
      (footprint "ws2812b")
      (libsource (lib "WTFschlibra") (part "Ws2812B"))
    )
    (comp (ref "LED42")
      (value "Ws2812B")
      (footprint "ws2812b")
      (libsource (lib "WTFschlibra") (part "Ws2812B"))
    )
    (comp (ref "LED43")
      (value "Ws2812B")
      (footprint "ws2812b")
      (libsource (lib "WTFschlibra") (part "Ws2812B"))
    )
    (comp (ref "LED44")
      (value "Ws2812B")
      (footprint "ws2812b")
      (libsource (lib "WTFschlibra") (part "Ws2812B"))
    )
    (comp (ref "LED45")
      (value "Ws2812B")
      (footprint "ws2812b")
      (libsource (lib "WTFschlibra") (part "Ws2812B"))
    )
    (comp (ref "LED46")
      (value "Ws2812B")
      (footprint "ws2812b")
      (libsource (lib "WTFschlibra") (part "Ws2812B"))
    )
    (comp (ref "LED47")
      (value "Ws2812B")
      (footprint "ws2812b")
      (libsource (lib "WTFschlibra") (part "Ws2812B"))
    )
    (comp (ref "LED48")
      (value "Ws2812B")
      (footprint "ws2812b")
      (libsource (lib "WTFschlibra") (part "Ws2812B"))
    )
    (comp (ref "LED49")
      (value "Ws2812B")
      (footprint "ws2812b")
      (libsource (lib "WTFschlibra") (part "Ws2812B"))
    )
    (comp (ref "LED50")
      (value "Ws2812B")
      (footprint "ws2812b")
      (libsource (lib "WTFschlibra") (part "Ws2812B"))
    )
    (comp (ref "LED51")
      (value "Ws2812B")
      (footprint "ws2812b")
      (libsource (lib "WTFschlibra") (part "Ws2812B"))
    )
    (comp (ref "LED52")
      (value "Ws2812B")
      (footprint "ws2812b")
      (libsource (lib "WTFschlibra") (part "Ws2812B"))
    )
    (comp (ref "LED53")
      (value "Ws2812B")
      (footprint "ws2812b")
      (libsource (lib "WTFschlibra") (part "Ws2812B"))
    )
    (comp (ref "LED54")
      (value "Ws2812B")
      (footprint "ws2812b")
      (libsource (lib "WTFschlibra") (part "Ws2812B"))
    )
    (comp (ref "LED55")
      (value "Ws2812B")
      (footprint "ws2812b")
      (libsource (lib "WTFschlibra") (part "Ws2812B"))
    )
    (comp (ref "LED56")
      (value "Ws2812B")
      (footprint "ws2812b")
      (libsource (lib "WTFschlibra") (part "Ws2812B"))
    )
    (comp (ref "LED57")
      (value "Ws2812B")
      (footprint "ws2812b")
      (libsource (lib "WTFschlibra") (part "Ws2812B"))
    )
    (comp (ref "LED58")
      (value "Ws2812B")
      (footprint "ws2812b")
      (libsource (lib "WTFschlibra") (part "Ws2812B"))
    )
    (comp (ref "LED59")
      (value "Ws2812B")
      (footprint "ws2812b")
      (libsource (lib "WTFschlibra") (part "Ws2812B"))
    )
    (comp (ref "LED60")
      (value "Ws2812B")
      (footprint "ws2812b")
      (libsource (lib "WTFschlibra") (part "Ws2812B"))
    )
    (comp (ref "LED61")
      (value "Ws2812B")
      (footprint "ws2812b")
      (libsource (lib "WTFschlibra") (part "Ws2812B"))
    )
    (comp (ref "LED62")
      (value "Ws2812B")
      (footprint "ws2812b")
      (libsource (lib "WTFschlibra") (part "Ws2812B"))
    )
    (comp (ref "LED63")
      (value "Ws2812B")
      (footprint "ws2812b")
      (libsource (lib "WTFschlibra") (part "Ws2812B"))
    )
    (comp (ref "LED64")
      (value "Ws2812B")
      (footprint "ws2812b")
      (libsource (lib "WTFschlibra") (part "Ws2812B"))
    )
    (comp (ref "LED65")
      (value "Ws2812B")
      (footprint "ws2812b")
      (libsource (lib "WTFschlibra") (part "Ws2812B"))
    )
    (comp (ref "LED66")
      (value "Ws2812B")
      (footprint "ws2812b")
      (libsource (lib "WTFschlibra") (part "Ws2812B"))
    )
    (comp (ref "LED67")
      (value "Ws2812B")
      (footprint "ws2812b")
      (libsource (lib "WTFschlibra") (part "Ws2812B"))
    )
    (comp (ref "LED68")
      (value "Ws2812B")
      (footprint "ws2812b")
      (libsource (lib "WTFschlibra") (part "Ws2812B"))
    )
    (comp (ref "LED69")
      (value "Ws2812B")
      (footprint "ws2812b")
      (libsource (lib "WTFschlibra") (part "Ws2812B"))
    )
    (comp (ref "LED70")
      (value "Ws2812B")
      (footprint "ws2812b")
      (libsource (lib "WTFschlibra") (part "Ws2812B"))
    )
    (comp (ref "LED71")
      (value "Ws2812B")
      (footprint "ws2812b")
      (libsource (lib "WTFschlibra") (part "Ws2812B"))
    )
    (comp (ref "LED72")
      (value "Ws2812B")
      (footprint "ws2812b")
      (libsource (lib "WTFschlibra") (part "Ws2812B"))
    )
    (comp (ref "LED73")
      (value "Ws2812B")
      (footprint "ws2812b")
      (libsource (lib "WTFschlibra") (part "Ws2812B"))
    )
    (comp (ref "LED74")
      (value "Ws2812B")
      (footprint "ws2812b")
      (libsource (lib "WTFschlibra") (part "Ws2812B"))
    )
    (comp (ref "LED75")
      (value "Ws2812B")
      (footprint "ws2812b")
      (libsource (lib "WTFschlibra") (part "Ws2812B"))
    )
    (comp (ref "LED76")
      (value "Ws2812B")
      (footprint "ws2812b")
      (libsource (lib "WTFschlibra") (part "Ws2812B"))
    )
    (comp (ref "LED77")
      (value "Ws2812B")
      (footprint "ws2812b")
      (libsource (lib "WTFschlibra") (part "Ws2812B"))
    )
    (comp (ref "LED78")
      (value "Ws2812B")
      (footprint "ws2812b")
      (libsource (lib "WTFschlibra") (part "Ws2812B"))
    )
    (comp (ref "LED79")
      (value "Ws2812B")
      (footprint "ws2812b")
      (libsource (lib "WTFschlibra") (part "Ws2812B"))
    )
    (comp (ref "LED80")
      (value "Ws2812B")
      (footprint "ws2812b")
      (libsource (lib "WTFschlibra") (part "Ws2812B"))
    )
    (comp (ref "LED81")
      (value "Ws2812B")
      (footprint "ws2812b")
      (libsource (lib "WTFschlibra") (part "Ws2812B"))
    )
    (comp (ref "LED82")
      (value "Ws2812B")
      (footprint "ws2812b")
      (libsource (lib "WTFschlibra") (part "Ws2812B"))
    )
    (comp (ref "LED83")
      (value "Ws2812B")
      (footprint "ws2812b")
      (libsource (lib "WTFschlibra") (part "Ws2812B"))
    )
    (comp (ref "LED84")
      (value "Ws2812B")
      (footprint "ws2812b")
      (libsource (lib "WTFschlibra") (part "Ws2812B"))
    )
    (comp (ref "LED85")
      (value "Ws2812B")
      (footprint "ws2812b")
      (libsource (lib "WTFschlibra") (part "Ws2812B"))
    )
    (comp (ref "LED86")
      (value "Ws2812B")
      (footprint "ws2812b")
      (libsource (lib "WTFschlibra") (part "Ws2812B"))
    )
    (comp (ref "LED87")
      (value "Ws2812B")
      (footprint "ws2812b")
      (libsource (lib "WTFschlibra") (part "Ws2812B"))
    )
    (comp (ref "LED88")
      (value "Ws2812B")
      (footprint "ws2812b")
      (libsource (lib "WTFschlibra") (part "Ws2812B"))
    )
    (comp (ref "LED89")
      (value "Ws2812B")
      (footprint "ws2812b")
      (libsource (lib "WTFschlibra") (part "Ws2812B"))
    )
    (comp (ref "LED90")
      (value "Ws2812B")
      (footprint "ws2812b")
      (libsource (lib "WTFschlibra") (part "Ws2812B"))
    )
    (comp (ref "LED91")
      (value "Ws2812B")
      (footprint "ws2812b")
      (libsource (lib "WTFschlibra") (part "Ws2812B"))
    )
    (comp (ref "LED92")
      (value "Ws2812B")
      (footprint "ws2812b")
      (libsource (lib "WTFschlibra") (part "Ws2812B"))
    )
    (comp (ref "LED93")
      (value "Ws2812B")
      (footprint "ws2812b")
      (libsource (lib "WTFschlibra") (part "Ws2812B"))
    )
    (comp (ref "LED94")
      (value "Ws2812B")
      (footprint "ws2812b")
      (libsource (lib "WTFschlibra") (part "Ws2812B"))
    )
    (comp (ref "LED95")
      (value "Ws2812B")
      (footprint "ws2812b")
      (libsource (lib "WTFschlibra") (part "Ws2812B"))
    )
    (comp (ref "LED96")
      (value "Ws2812B")
      (footprint "ws2812b")
      (libsource (lib "WTFschlibra") (part "Ws2812B"))
    )
    (comp (ref "LED97")
      (value "Ws2812B")
      (footprint "ws2812b")
      (libsource (lib "WTFschlibra") (part "Ws2812B"))
    )
    (comp (ref "LED98")
      (value "Ws2812B")
      (footprint "ws2812b")
      (libsource (lib "WTFschlibra") (part "Ws2812B"))
    )
    (comp (ref "LED99")
      (value "Ws2812B")
      (footprint "ws2812b")
      (libsource (lib "WTFschlibra") (part "Ws2812B"))
    )
    (comp (ref "LED100")
      (value "Ws2812B")
      (footprint "ws2812b")
      (libsource (lib "WTFschlibra") (part "Ws2812B"))
    )
    (comp (ref "LED101")
      (value "Ws2812B")
      (footprint "ws2812b")
      (libsource (lib "WTFschlibra") (part "Ws2812B"))
    )
    (comp (ref "LED102")
      (value "Ws2812B")
      (footprint "ws2812b")
      (libsource (lib "WTFschlibra") (part "Ws2812B"))
    )
    (comp (ref "LED103")
      (value "Ws2812B")
      (footprint "ws2812b")
      (libsource (lib "WTFschlibra") (part "Ws2812B"))
    )
    (comp (ref "LED104")
      (value "Ws2812B")
      (footprint "ws2812b")
      (libsource (lib "WTFschlibra") (part "Ws2812B"))
    )
    (comp (ref "LED105")
      (value "Ws2812B")
      (footprint "ws2812b")
      (libsource (lib "WTFschlibra") (part "Ws2812B"))
    )
    (comp (ref "LED106")
      (value "Ws2812B")
      (footprint "ws2812b")
      (libsource (lib "WTFschlibra") (part "Ws2812B"))
    )
    (comp (ref "LED107")
      (value "Ws2812B")
      (footprint "ws2812b")
      (libsource (lib "WTFschlibra") (part "Ws2812B"))
    )
    (comp (ref "LED108")
      (value "Ws2812B")
      (footprint "ws2812b")
      (libsource (lib "WTFschlibra") (part "Ws2812B"))
    )
    (comp (ref "LED109")
      (value "Ws2812B")
      (footprint "ws2812b")
      (libsource (lib "WTFschlibra") (part "Ws2812B"))
    )
    (comp (ref "LED110")
      (value "Ws2812B")
      (footprint "ws2812b")
      (libsource (lib "WTFschlibra") (part "Ws2812B"))
    )
    (comp (ref "LED111")
      (value "Ws2812B")
      (footprint "ws2812b")
      (libsource (lib "WTFschlibra") (part "Ws2812B"))
    )
    (comp (ref "LED112")
      (value "Ws2812B")
      (footprint "ws2812b")
      (libsource (lib "WTFschlibra") (part "Ws2812B"))
    )
    (comp (ref "P_ON")
      (value "Led")
      (footprint "LED0603")
      (description "LED BLUE CLEAR CHIP SMD")
      (libsource (lib "WTFschlibra") (part "LTST-C190TBKT"))
    )
    (comp (ref "R1")
      (value "102R")
      (footprint "R0805")
      (description "Res Thick Film 0805 360 Ohm 1% 0.125W(1/8W) ±100ppm/C Molded SMD Automotive Paper T/R")
      (fields (field (name "TOLERANCE") "1%"))
      (libsource (lib "WTFschlibra") (part "resistor(CRCW0805360RFKEA"))
    )
    (comp (ref "R2")
      (value "102R")
      (footprint "R0805")
      (description "Res Thick Film 0805 360 Ohm 1% 0.125W(1/8W) ±100ppm/C Molded SMD Automotive Paper T/R")
      (fields (field (name "TOLERANCE") "1%"))
      (libsource (lib "WTFschlibra") (part "resistor(CRCW0805360RFKEA"))
    )
    (comp (ref "R5")
      (value "102R")
      (footprint "R0805")
      (description "1Kohms")
      (fields (field (name "TOLERANCE") "1%"))
      (libsource (lib "WTFschlibra") (part "resistor(CRCW0805360RFKEA"))
    )
    (comp (ref "R6")
      (value "360R")
      (footprint "R0805")
      (description "Res Thick Film 0805 360 Ohm 1% 0.125W(1/8W) ±100ppm/C Molded SMD Automotive Paper T/R")
      (fields (field (name "TOLERANCE") "1%"))
      (libsource (lib "WTFschlibra") (part "CRCW0805360RFKEA"))
    )
    (comp (ref "R7")
      (value "360R")
      (footprint "R0805")
      (description "Res Thick Film 0805 360 Ohm 1% 0.125W(1/8W) ±100ppm/C Molded SMD Automotive Paper T/R")
      (fields (field (name "TOLERANCE") "1%"))
      (libsource (lib "WTFschlibra") (part "CRCW0805360RFKEA"))
    )
    (comp (ref "R8")
      (value "0R_or_360R")
      (footprint "R0805")
      (description "Res Thick Film 0805 360 Ohm 1% 0.125W(1/8W) ±100ppm/C Molded SMD Automotive Paper T/R")
      (fields (field (name "TOLERANCE") "1%"))
      (libsource (lib "WTFschlibra") (part "resistor(CRCW0805360RFKEA"))
    )
    (comp (ref "R9")
      (value "0R_or_360R")
      (footprint "R0805")
      (description "Res Thick Film 0805 360 Ohm 1% 0.125W(1/8W) ±100ppm/C Molded SMD Automotive Paper T/R")
      (fields (field (name "TOLERANCE") "1%"))
      (libsource (lib "WTFschlibra") (part "resistor(CRCW0805360RFKEA"))
    )
    (comp (ref "Relay1")
      (value "LM1H-12D")
      (footprint "Relay LM1H-12D")
      (libsource (lib "WTFschlibra") (part "LM1H-12D"))
    )
    (comp (ref "Screen")
      (value "1.44 Screen")
      (footprint "1.44TFT Screen")
      (libsource (lib "WTFschlibra") (part "1.44 st7735 TFT screen"))
    )
    (comp (ref "T1")
      (value "Touch_pads2x2")
      (footprint "TouchBoard2x2")
      (libsource (lib "WTFschlibra") (part "Touch_pads2x2"))
    )
    (comp (ref "T2")
      (value "Touch_pads2x2")
      (footprint "TouchBoard2x2")
      (libsource (lib "WTFschlibra") (part "Touch_pads2x2"))
    )
    (comp (ref "usb1")
      (value "usb_A_horizontal")
      (footprint "HORIZONTAL_USB_A_MALE_SOCKET")
      (description "4 Position Single Port Socket Right Angle Type A Through Hole USB")
      (libsource (lib "WTFschlibra") (part "usb_A_horizontal"))
    )
  )
  (nets
    (net (code "1") (name "+3.3") (class "Default")
      (node (ref "J2") (pin "1") (pinfunction "3v3_1") (pintype "power_in"))
      (node (ref "J7") (pin "3") (pinfunction "3v3_3") (pintype "passive"))
      (node (ref "R8") (pin "2") (pinfunction "2_2") (pintype "passive"))
      (node (ref "R9") (pin "2") (pinfunction "2_2") (pintype "passive"))
    )
    (net (code "2") (name "+5V") (class "Default")
      (node (ref "ADXL345") (pin "1") (pinfunction "5v_1") (pintype "passive"))
      (node (ref "C1") (pin "2") (pinfunction "+_2") (pintype "passive"))
      (node (ref "C10") (pin "2") (pinfunction "+_2") (pintype "passive"))
      (node (ref "C100") (pin "2") (pinfunction "+_2") (pintype "passive"))
      (node (ref "C101") (pin "2") (pinfunction "+_2") (pintype "passive"))
      (node (ref "C102") (pin "2") (pinfunction "+_2") (pintype "passive"))
      (node (ref "C103") (pin "2") (pinfunction "+_2") (pintype "passive"))
      (node (ref "C104") (pin "2") (pinfunction "+_2") (pintype "passive"))
      (node (ref "C105") (pin "2") (pinfunction "+_2") (pintype "passive"))
      (node (ref "C106") (pin "2") (pinfunction "+_2") (pintype "passive"))
      (node (ref "C107") (pin "2") (pinfunction "+_2") (pintype "passive"))
      (node (ref "C108") (pin "2") (pinfunction "+_2") (pintype "passive"))
      (node (ref "C109") (pin "2") (pinfunction "+_2") (pintype "passive"))
      (node (ref "C11") (pin "2") (pinfunction "+_2") (pintype "passive"))
      (node (ref "C110") (pin "2") (pinfunction "+_2") (pintype "passive"))
      (node (ref "C111") (pin "2") (pinfunction "+_2") (pintype "passive"))
      (node (ref "C112") (pin "2") (pinfunction "+_2") (pintype "passive"))
      (node (ref "C113") (pin "2") (pinfunction "+_2") (pintype "passive"))
      (node (ref "C114") (pin "2") (pinfunction "+_2") (pintype "passive"))
      (node (ref "C115") (pin "2") (pinfunction "+_2") (pintype "passive"))
      (node (ref "C116") (pin "2") (pinfunction "+_2") (pintype "passive"))
      (node (ref "C117") (pin "2") (pinfunction "+_2") (pintype "passive"))
      (node (ref "C118") (pin "2") (pinfunction "+_2") (pintype "passive"))
      (node (ref "C119") (pin "2") (pinfunction "+_2") (pintype "passive"))
      (node (ref "C12") (pin "2") (pinfunction "+_2") (pintype "passive"))
      (node (ref "C13") (pin "2") (pinfunction "+_2") (pintype "passive"))
      (node (ref "C14") (pin "2") (pinfunction "+_2") (pintype "passive"))
      (node (ref "C15") (pin "2") (pinfunction "+_2") (pintype "passive"))
      (node (ref "C16") (pin "2") (pinfunction "+_2") (pintype "passive"))
      (node (ref "C17") (pin "2") (pinfunction "+_2") (pintype "passive"))
      (node (ref "C18") (pin "2") (pinfunction "+_2") (pintype "passive"))
      (node (ref "C19") (pin "2") (pinfunction "+_2") (pintype "passive"))
      (node (ref "C2") (pin "2") (pinfunction "+_2") (pintype "passive"))
      (node (ref "C20") (pin "2") (pinfunction "+_2") (pintype "passive"))
      (node (ref "C21") (pin "2") (pinfunction "+_2") (pintype "passive"))
      (node (ref "C22") (pin "2") (pinfunction "+_2") (pintype "passive"))
      (node (ref "C23") (pin "2") (pinfunction "+_2") (pintype "passive"))
      (node (ref "C24") (pin "2") (pinfunction "+_2") (pintype "passive"))
      (node (ref "C25") (pin "2") (pinfunction "+_2") (pintype "passive"))
      (node (ref "C26") (pin "2") (pinfunction "+_2") (pintype "passive"))
      (node (ref "C27") (pin "2") (pinfunction "+_2") (pintype "passive"))
      (node (ref "C28") (pin "2") (pinfunction "+_2") (pintype "passive"))
      (node (ref "C29") (pin "2") (pinfunction "+_2") (pintype "passive"))
      (node (ref "C3") (pin "2") (pinfunction "+_2") (pintype "passive"))
      (node (ref "C30") (pin "2") (pinfunction "+_2") (pintype "passive"))
      (node (ref "C31") (pin "2") (pinfunction "+_2") (pintype "passive"))
      (node (ref "C32") (pin "2") (pinfunction "+_2") (pintype "passive"))
      (node (ref "C33") (pin "2") (pinfunction "+_2") (pintype "passive"))
      (node (ref "C34") (pin "2") (pinfunction "+_2") (pintype "passive"))
      (node (ref "C35") (pin "2") (pinfunction "+_2") (pintype "passive"))
      (node (ref "C36") (pin "2") (pinfunction "+_2") (pintype "passive"))
      (node (ref "C37") (pin "2") (pinfunction "+_2") (pintype "passive"))
      (node (ref "C38") (pin "2") (pinfunction "+_2") (pintype "passive"))
      (node (ref "C39") (pin "2") (pinfunction "+_2") (pintype "passive"))
      (node (ref "C4") (pin "2") (pinfunction "+_2") (pintype "passive"))
      (node (ref "C40") (pin "2") (pinfunction "+_2") (pintype "passive"))
      (node (ref "C41") (pin "2") (pinfunction "+_2") (pintype "passive"))
      (node (ref "C42") (pin "2") (pinfunction "+_2") (pintype "passive"))
      (node (ref "C43") (pin "2") (pinfunction "+_2") (pintype "passive"))
      (node (ref "C44") (pin "2") (pinfunction "+_2") (pintype "passive"))
      (node (ref "C45") (pin "2") (pinfunction "+_2") (pintype "passive"))
      (node (ref "C46") (pin "2") (pinfunction "+_2") (pintype "passive"))
      (node (ref "C47") (pin "2") (pinfunction "+_2") (pintype "passive"))
      (node (ref "C48") (pin "2") (pinfunction "+_2") (pintype "passive"))
      (node (ref "C49") (pin "2") (pinfunction "+_2") (pintype "passive"))
      (node (ref "C5") (pin "2") (pinfunction "+_2") (pintype "passive"))
      (node (ref "C50") (pin "2") (pinfunction "+_2") (pintype "passive"))
      (node (ref "C51") (pin "2") (pinfunction "+_2") (pintype "passive"))
      (node (ref "C52") (pin "2") (pinfunction "+_2") (pintype "passive"))
      (node (ref "C53") (pin "2") (pinfunction "+_2") (pintype "passive"))
      (node (ref "C54") (pin "2") (pinfunction "+_2") (pintype "passive"))
      (node (ref "C55") (pin "2") (pinfunction "+_2") (pintype "passive"))
      (node (ref "C56") (pin "2") (pinfunction "+_2") (pintype "passive"))
      (node (ref "C57") (pin "2") (pinfunction "+_2") (pintype "passive"))
      (node (ref "C58") (pin "2") (pinfunction "+_2") (pintype "passive"))
      (node (ref "C59") (pin "2") (pinfunction "+_2") (pintype "passive"))
      (node (ref "C6") (pin "2") (pinfunction "+_2") (pintype "passive"))
      (node (ref "C60") (pin "2") (pinfunction "+_2") (pintype "passive"))
      (node (ref "C61") (pin "2") (pinfunction "+_2") (pintype "passive"))
      (node (ref "C62") (pin "2") (pinfunction "+_2") (pintype "passive"))
      (node (ref "C63") (pin "2") (pinfunction "+_2") (pintype "passive"))
      (node (ref "C68") (pin "2") (pinfunction "+_2") (pintype "passive"))
      (node (ref "C69") (pin "2") (pinfunction "+_2") (pintype "passive"))
      (node (ref "C7") (pin "2") (pinfunction "+_2") (pintype "passive"))
      (node (ref "C70") (pin "2") (pinfunction "+_2") (pintype "passive"))
      (node (ref "C71") (pin "2") (pinfunction "+_2") (pintype "passive"))
      (node (ref "C72") (pin "2") (pinfunction "+_2") (pintype "passive"))
      (node (ref "C73") (pin "2") (pinfunction "+_2") (pintype "passive"))
      (node (ref "C74") (pin "2") (pinfunction "+_2") (pintype "passive"))
      (node (ref "C75") (pin "2") (pinfunction "+_2") (pintype "passive"))
      (node (ref "C76") (pin "2") (pinfunction "+_2") (pintype "passive"))
      (node (ref "C77") (pin "2") (pinfunction "+_2") (pintype "passive"))
      (node (ref "C78") (pin "2") (pinfunction "+_2") (pintype "passive"))
      (node (ref "C79") (pin "2") (pinfunction "+_2") (pintype "passive"))
      (node (ref "C8") (pin "2") (pinfunction "+_2") (pintype "passive"))
      (node (ref "C80") (pin "2") (pinfunction "+_2") (pintype "passive"))
      (node (ref "C81") (pin "2") (pinfunction "+_2") (pintype "passive"))
      (node (ref "C82") (pin "2") (pinfunction "+_2") (pintype "passive"))
      (node (ref "C83") (pin "2") (pinfunction "+_2") (pintype "passive"))
      (node (ref "C84") (pin "2") (pinfunction "+_2") (pintype "passive"))
      (node (ref "C85") (pin "2") (pinfunction "+_2") (pintype "passive"))
      (node (ref "C86") (pin "2") (pinfunction "+_2") (pintype "passive"))
      (node (ref "C87") (pin "2") (pinfunction "+_2") (pintype "passive"))
      (node (ref "C88") (pin "2") (pinfunction "+_2") (pintype "passive"))
      (node (ref "C89") (pin "2") (pinfunction "+_2") (pintype "passive"))
      (node (ref "C9") (pin "2") (pinfunction "+_2") (pintype "passive"))
      (node (ref "C90") (pin "2") (pinfunction "+_2") (pintype "passive"))
      (node (ref "C91") (pin "2") (pinfunction "+_2") (pintype "passive"))
      (node (ref "C92") (pin "2") (pinfunction "+_2") (pintype "passive"))
      (node (ref "C93") (pin "2") (pinfunction "+_2") (pintype "passive"))
      (node (ref "C94") (pin "2") (pinfunction "+_2") (pintype "passive"))
      (node (ref "C95") (pin "2") (pinfunction "+_2") (pintype "passive"))
      (node (ref "C96") (pin "2") (pinfunction "+_2") (pintype "passive"))
      (node (ref "C97") (pin "2") (pinfunction "+_2") (pintype "passive"))
      (node (ref "C98") (pin "2") (pinfunction "+_2") (pintype "passive"))
      (node (ref "C99") (pin "2") (pinfunction "+_2") (pintype "passive"))
      (node (ref "J1") (pin "2") (pinfunction "VCC_2") (pintype "power_in"))
      (node (ref "J2") (pin "4") (pinfunction "5v_4") (pintype "power_in"))
      (node (ref "J3") (pin "1") (pinfunction "5V_1") (pintype "passive"))
      (node (ref "J7") (pin "2") (pinfunction "5v_2") (pintype "passive"))
      (node (ref "LED1") (pin "1") (pinfunction "VDD_1") (pintype "passive"))
      (node (ref "LED10") (pin "1") (pinfunction "VDD_1") (pintype "passive"))
      (node (ref "LED100") (pin "1") (pinfunction "VDD_1") (pintype "passive"))
      (node (ref "LED101") (pin "1") (pinfunction "VDD_1") (pintype "passive"))
      (node (ref "LED102") (pin "1") (pinfunction "VDD_1") (pintype "passive"))
      (node (ref "LED103") (pin "1") (pinfunction "VDD_1") (pintype "passive"))
      (node (ref "LED104") (pin "1") (pinfunction "VDD_1") (pintype "passive"))
      (node (ref "LED105") (pin "1") (pinfunction "VDD_1") (pintype "passive"))
      (node (ref "LED106") (pin "1") (pinfunction "VDD_1") (pintype "passive"))
      (node (ref "LED107") (pin "1") (pinfunction "VDD_1") (pintype "passive"))
      (node (ref "LED108") (pin "1") (pinfunction "VDD_1") (pintype "passive"))
      (node (ref "LED109") (pin "1") (pinfunction "VDD_1") (pintype "passive"))
      (node (ref "LED11") (pin "1") (pinfunction "VDD_1") (pintype "passive"))
      (node (ref "LED110") (pin "1") (pinfunction "VDD_1") (pintype "passive"))
      (node (ref "LED111") (pin "1") (pinfunction "VDD_1") (pintype "passive"))
      (node (ref "LED112") (pin "1") (pinfunction "VDD_1") (pintype "passive"))
      (node (ref "LED12") (pin "1") (pinfunction "VDD_1") (pintype "passive"))
      (node (ref "LED13") (pin "1") (pinfunction "VDD_1") (pintype "passive"))
      (node (ref "LED14") (pin "1") (pinfunction "VDD_1") (pintype "passive"))
      (node (ref "LED15") (pin "1") (pinfunction "VDD_1") (pintype "passive"))
      (node (ref "LED16") (pin "1") (pinfunction "VDD_1") (pintype "passive"))
      (node (ref "LED17") (pin "1") (pinfunction "VDD_1") (pintype "passive"))
      (node (ref "LED18") (pin "1") (pinfunction "VDD_1") (pintype "passive"))
      (node (ref "LED19") (pin "1") (pinfunction "VDD_1") (pintype "passive"))
      (node (ref "LED2") (pin "1") (pinfunction "VDD_1") (pintype "passive"))
      (node (ref "LED20") (pin "1") (pinfunction "VDD_1") (pintype "passive"))
      (node (ref "LED21") (pin "1") (pinfunction "VDD_1") (pintype "passive"))
      (node (ref "LED22") (pin "1") (pinfunction "VDD_1") (pintype "passive"))
      (node (ref "LED23") (pin "1") (pinfunction "VDD_1") (pintype "passive"))
      (node (ref "LED24") (pin "1") (pinfunction "VDD_1") (pintype "passive"))
      (node (ref "LED25") (pin "1") (pinfunction "VDD_1") (pintype "passive"))
      (node (ref "LED26") (pin "1") (pinfunction "VDD_1") (pintype "passive"))
      (node (ref "LED27") (pin "1") (pinfunction "VDD_1") (pintype "passive"))
      (node (ref "LED28") (pin "1") (pinfunction "VDD_1") (pintype "passive"))
      (node (ref "LED29") (pin "1") (pinfunction "VDD_1") (pintype "passive"))
      (node (ref "LED3") (pin "1") (pinfunction "VDD_1") (pintype "passive"))
      (node (ref "LED30") (pin "1") (pinfunction "VDD_1") (pintype "passive"))
      (node (ref "LED31") (pin "1") (pinfunction "VDD_1") (pintype "passive"))
      (node (ref "LED32") (pin "1") (pinfunction "VDD_1") (pintype "passive"))
      (node (ref "LED33") (pin "1") (pinfunction "VDD_1") (pintype "passive"))
      (node (ref "LED34") (pin "1") (pinfunction "VDD_1") (pintype "passive"))
      (node (ref "LED35") (pin "1") (pinfunction "VDD_1") (pintype "passive"))
      (node (ref "LED36") (pin "1") (pinfunction "VDD_1") (pintype "passive"))
      (node (ref "LED37") (pin "1") (pinfunction "VDD_1") (pintype "passive"))
      (node (ref "LED38") (pin "1") (pinfunction "VDD_1") (pintype "passive"))
      (node (ref "LED39") (pin "1") (pinfunction "VDD_1") (pintype "passive"))
      (node (ref "LED4") (pin "1") (pinfunction "VDD_1") (pintype "passive"))
      (node (ref "LED40") (pin "1") (pinfunction "VDD_1") (pintype "passive"))
      (node (ref "LED41") (pin "1") (pinfunction "VDD_1") (pintype "passive"))
      (node (ref "LED42") (pin "1") (pinfunction "VDD_1") (pintype "passive"))
      (node (ref "LED43") (pin "1") (pinfunction "VDD_1") (pintype "passive"))
      (node (ref "LED44") (pin "1") (pinfunction "VDD_1") (pintype "passive"))
      (node (ref "LED45") (pin "1") (pinfunction "VDD_1") (pintype "passive"))
      (node (ref "LED46") (pin "1") (pinfunction "VDD_1") (pintype "passive"))
      (node (ref "LED47") (pin "1") (pinfunction "VDD_1") (pintype "passive"))
      (node (ref "LED48") (pin "1") (pinfunction "VDD_1") (pintype "passive"))
      (node (ref "LED49") (pin "1") (pinfunction "VDD_1") (pintype "passive"))
      (node (ref "LED5") (pin "1") (pinfunction "VDD_1") (pintype "passive"))
      (node (ref "LED50") (pin "1") (pinfunction "VDD_1") (pintype "passive"))
      (node (ref "LED51") (pin "1") (pinfunction "VDD_1") (pintype "passive"))
      (node (ref "LED52") (pin "1") (pinfunction "VDD_1") (pintype "passive"))
      (node (ref "LED53") (pin "1") (pinfunction "VDD_1") (pintype "passive"))
      (node (ref "LED54") (pin "1") (pinfunction "VDD_1") (pintype "passive"))
      (node (ref "LED55") (pin "1") (pinfunction "VDD_1") (pintype "passive"))
      (node (ref "LED56") (pin "1") (pinfunction "VDD_1") (pintype "passive"))
      (node (ref "LED57") (pin "1") (pinfunction "VDD_1") (pintype "passive"))
      (node (ref "LED58") (pin "1") (pinfunction "VDD_1") (pintype "passive"))
      (node (ref "LED59") (pin "1") (pinfunction "VDD_1") (pintype "passive"))
      (node (ref "LED6") (pin "1") (pinfunction "VDD_1") (pintype "passive"))
      (node (ref "LED60") (pin "1") (pinfunction "VDD_1") (pintype "passive"))
      (node (ref "LED61") (pin "1") (pinfunction "VDD_1") (pintype "passive"))
      (node (ref "LED62") (pin "1") (pinfunction "VDD_1") (pintype "passive"))
      (node (ref "LED63") (pin "1") (pinfunction "VDD_1") (pintype "passive"))
      (node (ref "LED64") (pin "1") (pinfunction "VDD_1") (pintype "passive"))
      (node (ref "LED65") (pin "1") (pinfunction "VDD_1") (pintype "passive"))
      (node (ref "LED66") (pin "1") (pinfunction "VDD_1") (pintype "passive"))
      (node (ref "LED67") (pin "1") (pinfunction "VDD_1") (pintype "passive"))
      (node (ref "LED68") (pin "1") (pinfunction "VDD_1") (pintype "passive"))
      (node (ref "LED69") (pin "1") (pinfunction "VDD_1") (pintype "passive"))
      (node (ref "LED7") (pin "1") (pinfunction "VDD_1") (pintype "passive"))
      (node (ref "LED70") (pin "1") (pinfunction "VDD_1") (pintype "passive"))
      (node (ref "LED71") (pin "1") (pinfunction "VDD_1") (pintype "passive"))
      (node (ref "LED72") (pin "1") (pinfunction "VDD_1") (pintype "passive"))
      (node (ref "LED73") (pin "1") (pinfunction "VDD_1") (pintype "passive"))
      (node (ref "LED74") (pin "1") (pinfunction "VDD_1") (pintype "passive"))
      (node (ref "LED75") (pin "1") (pinfunction "VDD_1") (pintype "passive"))
      (node (ref "LED76") (pin "1") (pinfunction "VDD_1") (pintype "passive"))
      (node (ref "LED77") (pin "1") (pinfunction "VDD_1") (pintype "passive"))
      (node (ref "LED78") (pin "1") (pinfunction "VDD_1") (pintype "passive"))
      (node (ref "LED79") (pin "1") (pinfunction "VDD_1") (pintype "passive"))
      (node (ref "LED8") (pin "1") (pinfunction "VDD_1") (pintype "passive"))
      (node (ref "LED80") (pin "1") (pinfunction "VDD_1") (pintype "passive"))
      (node (ref "LED81") (pin "1") (pinfunction "VDD_1") (pintype "passive"))
      (node (ref "LED82") (pin "1") (pinfunction "VDD_1") (pintype "passive"))
      (node (ref "LED83") (pin "1") (pinfunction "VDD_1") (pintype "passive"))
      (node (ref "LED84") (pin "1") (pinfunction "VDD_1") (pintype "passive"))
      (node (ref "LED85") (pin "1") (pinfunction "VDD_1") (pintype "passive"))
      (node (ref "LED86") (pin "1") (pinfunction "VDD_1") (pintype "passive"))
      (node (ref "LED87") (pin "1") (pinfunction "VDD_1") (pintype "passive"))
      (node (ref "LED88") (pin "1") (pinfunction "VDD_1") (pintype "passive"))
      (node (ref "LED89") (pin "1") (pinfunction "VDD_1") (pintype "passive"))
      (node (ref "LED9") (pin "1") (pinfunction "VDD_1") (pintype "passive"))
      (node (ref "LED90") (pin "1") (pinfunction "VDD_1") (pintype "passive"))
      (node (ref "LED91") (pin "1") (pinfunction "VDD_1") (pintype "passive"))
      (node (ref "LED92") (pin "1") (pinfunction "VDD_1") (pintype "passive"))
      (node (ref "LED93") (pin "1") (pinfunction "VDD_1") (pintype "passive"))
      (node (ref "LED94") (pin "1") (pinfunction "VDD_1") (pintype "passive"))
      (node (ref "LED95") (pin "1") (pinfunction "VDD_1") (pintype "passive"))
      (node (ref "LED96") (pin "1") (pinfunction "VDD_1") (pintype "passive"))
      (node (ref "LED97") (pin "1") (pinfunction "VDD_1") (pintype "passive"))
      (node (ref "LED98") (pin "1") (pinfunction "VDD_1") (pintype "passive"))
      (node (ref "LED99") (pin "1") (pinfunction "VDD_1") (pintype "passive"))
      (node (ref "P_ON") (pin "2") (pinfunction "2_2") (pintype "passive"))
      (node (ref "R1") (pin "2") (pinfunction "2_2") (pintype "passive"))
      (node (ref "R2") (pin "2") (pinfunction "2_2") (pintype "passive"))
      (node (ref "Relay1") (pin "4") (pinfunction "NO_4") (pintype "passive"))
      (node (ref "T1") (pin "1") (pinfunction "VCC_1") (pintype "passive"))
      (node (ref "T1") (pin "10") (pinfunction "VCC_10") (pintype "passive"))
      (node (ref "T1") (pin "4") (pinfunction "VCC_4") (pintype "passive"))
      (node (ref "T1") (pin "7") (pinfunction "VCC_7") (pintype "passive"))
      (node (ref "T2") (pin "1") (pinfunction "VCC_1") (pintype "passive"))
      (node (ref "T2") (pin "10") (pinfunction "VCC_10") (pintype "passive"))
      (node (ref "T2") (pin "4") (pinfunction "VCC_4") (pintype "passive"))
      (node (ref "T2") (pin "7") (pinfunction "VCC_7") (pintype "passive"))
      (node (ref "irl") (pin "2") (pinfunction "Drain_2") (pintype "passive"))
    )
    (net (code "3") (name "+12V") (class "Default")
      (node (ref "J2") (pin "6") (pinfunction "12v_6") (pintype "power_in"))
      (node (ref "J7") (pin "1") (pinfunction "12v_1") (pintype "passive"))
      (node (ref "Relay1") (pin "1") (pinfunction "Coli_A_1") (pintype "passive"))
    )
    (net (code "4") (name "/BD_DOUT") (class "Default")
      (node (ref "J3") (pin "4") (pinfunction "BD_DOUT_4") (pintype "passive"))
      (node (ref "LED112") (pin "2") (pinfunction "DOUT_2") (pintype "passive"))
    )
    (net (code "5") (name "/DA_FAN") (class "Default")
      (node (ref "esp1") (pin "33") (pinfunction "12_33") (pintype "bidirectional"))
      (node (ref "irl") (pin "1") (pinfunction "Gate_1") (pintype "passive"))
    )
    (net (code "6") (name "/DTR_IO0") (class "Default")
      (node (ref "cp1") (pin "28") (pinfunction "DTR_28") (pintype "passive"))
      (node (ref "esp1") (pin "17") (pinfunction "0_17") (pintype "bidirectional"))
    )
    (net (code "7") (name "/I2C_CLK") (class "Default")
      (node (ref "ADXL345") (pin "3") (pinfunction "SCL_3") (pintype "passive"))
      (node (ref "J5") (pin "1") (pinfunction "SCL_1") (pintype "passive"))
      (node (ref "esp1") (pin "5") (pinfunction "22_5") (pintype "bidirectional"))
    )
    (net (code "8") (name "/I2C_DA") (class "Default")
      (node (ref "ADXL345") (pin "4") (pinfunction "SDA_4") (pintype "passive"))
      (node (ref "J5") (pin "2") (pinfunction "SCk_2") (pintype "passive"))
      (node (ref "esp1") (pin "6") (pinfunction "21_6") (pintype "bidirectional"))
    )
    (net (code "9") (name "/IO_4") (class "Default")
      (node (ref "J6") (pin "7") (pinfunction "4_7") (pintype "passive"))
      (node (ref "esp1") (pin "16") (pinfunction "4_16") (pintype "bidirectional"))
    )
    (net (code "10") (name "/IO_13") (class "Default")
      (node (ref "J6") (pin "5") (pinfunction "13_5") (pintype "passive"))
      (node (ref "esp1") (pin "34") (pinfunction "13_34") (pintype "bidirectional"))
    )
    (net (code "11") (name "/IO_14") (class "Default")
      (node (ref "J6") (pin "4") (pinfunction "14_4") (pintype "passive"))
      (node (ref "esp1") (pin "32") (pinfunction "14_32") (pintype "bidirectional"))
    )
    (net (code "12") (name "/IO_15") (class "Default")
      (node (ref "J6") (pin "8") (pinfunction "15_8") (pintype "passive"))
      (node (ref "esp1") (pin "20") (pinfunction "15_20") (pintype "bidirectional"))
    )
    (net (code "13") (name "/IO_16") (class "Default")
      (node (ref "J6") (pin "6") (pinfunction "16_6") (pintype "passive"))
      (node (ref "esp1") (pin "15") (pinfunction "16_15") (pintype "bidirectional"))
    )
    (net (code "14") (name "/IO_34") (class "Default")
      (node (ref "J6") (pin "3") (pinfunction "34_3") (pintype "passive"))
      (node (ref "esp1") (pin "27") (pinfunction "34_27") (pintype "bidirectional"))
    )
    (net (code "15") (name "/IO_36") (class "Default")
      (node (ref "J6") (pin "1") (pinfunction "36_1") (pintype "passive"))
      (node (ref "esp1") (pin "23") (pinfunction "36/VP_23") (pintype "bidirectional"))
    )
    (net (code "16") (name "/IO_39") (class "Default")
      (node (ref "J6") (pin "2") (pinfunction "39_2") (pintype "passive"))
      (node (ref "esp1") (pin "24") (pinfunction "39/VN_24") (pintype "bidirectional"))
    )
    (net (code "17") (name "/Neopixel_DIN") (class "Default")
      (node (ref "J3") (pin "2") (pinfunction "DIN_2") (pintype "passive"))
      (node (ref "LED1") (pin "4") (pinfunction "DIN_4") (pintype "passive"))
      (node (ref "esp1") (pin "31") (pinfunction "27_31") (pintype "bidirectional"))
    )
    (net (code "18") (name "/RTS_EN") (class "Default")
      (node (ref "cp1") (pin "24") (pinfunction "RTS_24") (pintype "passive"))
      (node (ref "esp1") (pin "22") (pinfunction "EN_22") (pintype "passive"))
    )
    (net (code "19") (name "/RX") (class "Default")
      (node (ref "J8") (pin "2") (pinfunction "RX_2") (pintype "passive"))
      (node (ref "cp1") (pin "26") (pinfunction "TXD_26") (pintype "passive"))
      (node (ref "esp1") (pin "3") (pinfunction "RX_3") (pintype "passive"))
    )
    (net (code "20") (name "/SPI_CLK") (class "Default")
      (node (ref "J4") (pin "1") (pinfunction "SCK_1") (pintype "passive"))
      (node (ref "Screen") (pin "7") (pinfunction "SCK_7") (pintype "passive"))
      (node (ref "esp1") (pin "11") (pinfunction "18_11") (pintype "bidirectional"))
    )
    (net (code "21") (name "/SPI_MISO") (class "Default")
      (node (ref "J4") (pin "3") (pinfunction "MISO_3") (pintype "passive"))
      (node (ref "esp1") (pin "9") (pinfunction "19_9") (pintype "bidirectional"))
    )
    (net (code "22") (name "/SPI_MOSI") (class "Default")
      (node (ref "J4") (pin "2") (pinfunction "MOSI_2") (pintype "passive"))
      (node (ref "Screen") (pin "6") (pinfunction "SDA_6") (pintype "passive"))
      (node (ref "esp1") (pin "10") (pinfunction "23_10") (pintype "bidirectional"))
    )
    (net (code "23") (name "/TFT_CS") (class "Default")
      (node (ref "Screen") (pin "3") (pinfunction "CS_3") (pintype "passive"))
      (node (ref "esp1") (pin "12") (pinfunction "5_12") (pintype "bidirectional"))
    )
    (net (code "24") (name "/TFT_DC") (class "Default")
      (node (ref "Screen") (pin "5") (pinfunction "A0_5") (pintype "passive"))
      (node (ref "esp1") (pin "14") (pinfunction "17_14") (pintype "bidirectional"))
    )
    (net (code "25") (name "/TFT_RST") (class "Default")
      (node (ref "Screen") (pin "4") (pinfunction "RST_4") (pintype "passive"))
      (node (ref "esp1") (pin "19") (pinfunction "2_19") (pintype "bidirectional"))
    )
    (net (code "26") (name "/TX") (class "Default")
      (node (ref "J8") (pin "1") (pinfunction "TX_1") (pintype "passive"))
      (node (ref "cp1") (pin "25") (pinfunction "RXD_25") (pintype "passive"))
      (node (ref "esp1") (pin "2") (pinfunction "TX_2") (pintype "passive"))
    )
    (net (code "27") (name "/ab_encode_CLK") (class "Default")
      (node (ref "J1") (pin "5") (pinfunction "CLK_5") (pintype "bidirectional"))
      (node (ref "esp1") (pin "29") (pinfunction "25_29") (pintype "bidirectional"))
    )
    (net (code "28") (name "/ab_encode_CS") (class "Default")
      (node (ref "J1") (pin "4") (pinfunction "CS_4") (pintype "bidirectional"))
      (node (ref "esp1") (pin "30") (pinfunction "26_30") (pintype "bidirectional"))
    )
    (net (code "29") (name "/ab_encode_D0") (class "Default")
      (node (ref "J1") (pin "1") (pinfunction "D0_1") (pintype "bidirectional"))
      (node (ref "esp1") (pin "28") (pinfunction "35_28") (pintype "bidirectional"))
    )
    (net (code "30") (name "/touchboard_A") (class "Default")
      (node (ref "D1") (pin "2") (pinfunction "2_2") (pintype "passive"))
      (node (ref "D2") (pin "2") (pinfunction "2_2") (pintype "passive"))
      (node (ref "D3") (pin "2") (pinfunction "2_2") (pintype "passive"))
      (node (ref "D4") (pin "2") (pinfunction "2_2") (pintype "passive"))
      (node (ref "R1") (pin "1") (pinfunction "1_1") (pintype "passive"))
      (node (ref "esp1") (pin "25") (pinfunction "32_25") (pintype "bidirectional"))
    )
    (net (code "31") (name "/touchboard_B") (class "Default")
      (node (ref "D5") (pin "2") (pinfunction "2_2") (pintype "passive"))
      (node (ref "D6") (pin "2") (pinfunction "2_2") (pintype "passive"))
      (node (ref "D7") (pin "2") (pinfunction "2_2") (pintype "passive"))
      (node (ref "D8") (pin "2") (pinfunction "2_2") (pintype "passive"))
      (node (ref "R2") (pin "1") (pinfunction "1_1") (pintype "passive"))
      (node (ref "esp1") (pin "26") (pinfunction "33_26") (pintype "bidirectional"))
    )
    (net (code "32") (name "GND") (class "Default")
      (node (ref "473R") (pin "1") (pinfunction "1_1") (pintype "passive"))
      (node (ref "ADXL345") (pin "2") (pinfunction "GND_2") (pintype "passive"))
      (node (ref "C1") (pin "1") (pinfunction "-_1") (pintype "passive"))
      (node (ref "C10") (pin "1") (pinfunction "-_1") (pintype "passive"))
      (node (ref "C100") (pin "1") (pinfunction "-_1") (pintype "passive"))
      (node (ref "C101") (pin "1") (pinfunction "-_1") (pintype "passive"))
      (node (ref "C102") (pin "1") (pinfunction "-_1") (pintype "passive"))
      (node (ref "C103") (pin "1") (pinfunction "-_1") (pintype "passive"))
      (node (ref "C104") (pin "1") (pinfunction "-_1") (pintype "passive"))
      (node (ref "C105") (pin "1") (pinfunction "-_1") (pintype "passive"))
      (node (ref "C106") (pin "1") (pinfunction "-_1") (pintype "passive"))
      (node (ref "C107") (pin "1") (pinfunction "-_1") (pintype "passive"))
      (node (ref "C108") (pin "1") (pinfunction "-_1") (pintype "passive"))
      (node (ref "C109") (pin "1") (pinfunction "-_1") (pintype "passive"))
      (node (ref "C11") (pin "1") (pinfunction "-_1") (pintype "passive"))
      (node (ref "C110") (pin "1") (pinfunction "-_1") (pintype "passive"))
      (node (ref "C111") (pin "1") (pinfunction "-_1") (pintype "passive"))
      (node (ref "C112") (pin "1") (pinfunction "-_1") (pintype "passive"))
      (node (ref "C113") (pin "1") (pinfunction "-_1") (pintype "passive"))
      (node (ref "C114") (pin "1") (pinfunction "-_1") (pintype "passive"))
      (node (ref "C115") (pin "1") (pinfunction "-_1") (pintype "passive"))
      (node (ref "C116") (pin "1") (pinfunction "-_1") (pintype "passive"))
      (node (ref "C117") (pin "1") (pinfunction "-_1") (pintype "passive"))
      (node (ref "C118") (pin "1") (pinfunction "-_1") (pintype "passive"))
      (node (ref "C119") (pin "1") (pinfunction "-_1") (pintype "passive"))
      (node (ref "C12") (pin "1") (pinfunction "-_1") (pintype "passive"))
      (node (ref "C13") (pin "1") (pinfunction "-_1") (pintype "passive"))
      (node (ref "C14") (pin "1") (pinfunction "-_1") (pintype "passive"))
      (node (ref "C15") (pin "1") (pinfunction "-_1") (pintype "passive"))
      (node (ref "C16") (pin "1") (pinfunction "-_1") (pintype "passive"))
      (node (ref "C17") (pin "1") (pinfunction "-_1") (pintype "passive"))
      (node (ref "C18") (pin "1") (pinfunction "-_1") (pintype "passive"))
      (node (ref "C19") (pin "1") (pinfunction "-_1") (pintype "passive"))
      (node (ref "C2") (pin "1") (pinfunction "-_1") (pintype "passive"))
      (node (ref "C20") (pin "1") (pinfunction "-_1") (pintype "passive"))
      (node (ref "C21") (pin "1") (pinfunction "-_1") (pintype "passive"))
      (node (ref "C22") (pin "1") (pinfunction "-_1") (pintype "passive"))
      (node (ref "C23") (pin "1") (pinfunction "-_1") (pintype "passive"))
      (node (ref "C24") (pin "1") (pinfunction "-_1") (pintype "passive"))
      (node (ref "C25") (pin "1") (pinfunction "-_1") (pintype "passive"))
      (node (ref "C26") (pin "1") (pinfunction "-_1") (pintype "passive"))
      (node (ref "C27") (pin "1") (pinfunction "-_1") (pintype "passive"))
      (node (ref "C28") (pin "1") (pinfunction "-_1") (pintype "passive"))
      (node (ref "C29") (pin "1") (pinfunction "-_1") (pintype "passive"))
      (node (ref "C3") (pin "1") (pinfunction "-_1") (pintype "passive"))
      (node (ref "C30") (pin "1") (pinfunction "-_1") (pintype "passive"))
      (node (ref "C31") (pin "1") (pinfunction "-_1") (pintype "passive"))
      (node (ref "C32") (pin "1") (pinfunction "-_1") (pintype "passive"))
      (node (ref "C33") (pin "1") (pinfunction "-_1") (pintype "passive"))
      (node (ref "C34") (pin "1") (pinfunction "-_1") (pintype "passive"))
      (node (ref "C35") (pin "1") (pinfunction "-_1") (pintype "passive"))
      (node (ref "C36") (pin "1") (pinfunction "-_1") (pintype "passive"))
      (node (ref "C37") (pin "1") (pinfunction "-_1") (pintype "passive"))
      (node (ref "C38") (pin "1") (pinfunction "-_1") (pintype "passive"))
      (node (ref "C39") (pin "1") (pinfunction "-_1") (pintype "passive"))
      (node (ref "C4") (pin "1") (pinfunction "-_1") (pintype "passive"))
      (node (ref "C40") (pin "1") (pinfunction "-_1") (pintype "passive"))
      (node (ref "C41") (pin "1") (pinfunction "-_1") (pintype "passive"))
      (node (ref "C42") (pin "1") (pinfunction "-_1") (pintype "passive"))
      (node (ref "C43") (pin "1") (pinfunction "-_1") (pintype "passive"))
      (node (ref "C44") (pin "1") (pinfunction "-_1") (pintype "passive"))
      (node (ref "C45") (pin "1") (pinfunction "-_1") (pintype "passive"))
      (node (ref "C46") (pin "1") (pinfunction "-_1") (pintype "passive"))
      (node (ref "C47") (pin "1") (pinfunction "-_1") (pintype "passive"))
      (node (ref "C48") (pin "1") (pinfunction "-_1") (pintype "passive"))
      (node (ref "C49") (pin "1") (pinfunction "-_1") (pintype "passive"))
      (node (ref "C5") (pin "1") (pinfunction "-_1") (pintype "passive"))
      (node (ref "C50") (pin "1") (pinfunction "-_1") (pintype "passive"))
      (node (ref "C51") (pin "1") (pinfunction "-_1") (pintype "passive"))
      (node (ref "C52") (pin "1") (pinfunction "-_1") (pintype "passive"))
      (node (ref "C53") (pin "1") (pinfunction "-_1") (pintype "passive"))
      (node (ref "C54") (pin "1") (pinfunction "-_1") (pintype "passive"))
      (node (ref "C55") (pin "1") (pinfunction "-_1") (pintype "passive"))
      (node (ref "C56") (pin "1") (pinfunction "-_1") (pintype "passive"))
      (node (ref "C57") (pin "1") (pinfunction "-_1") (pintype "passive"))
      (node (ref "C58") (pin "1") (pinfunction "-_1") (pintype "passive"))
      (node (ref "C59") (pin "1") (pinfunction "-_1") (pintype "passive"))
      (node (ref "C6") (pin "1") (pinfunction "-_1") (pintype "passive"))
      (node (ref "C60") (pin "1") (pinfunction "-_1") (pintype "passive"))
      (node (ref "C61") (pin "1") (pinfunction "-_1") (pintype "passive"))
      (node (ref "C62") (pin "1") (pinfunction "-_1") (pintype "passive"))
      (node (ref "C63") (pin "1") (pinfunction "-_1") (pintype "passive"))
      (node (ref "C64") (pin "1") (pinfunction "-_1") (pintype "passive"))
      (node (ref "C65") (pin "1") (pinfunction "-_1") (pintype "passive"))
      (node (ref "C66") (pin "1") (pinfunction "-_1") (pintype "passive"))
      (node (ref "C67") (pin "1") (pinfunction "-_1") (pintype "passive"))
      (node (ref "C68") (pin "1") (pinfunction "-_1") (pintype "passive"))
      (node (ref "C69") (pin "1") (pinfunction "-_1") (pintype "passive"))
      (node (ref "C7") (pin "1") (pinfunction "-_1") (pintype "passive"))
      (node (ref "C70") (pin "1") (pinfunction "-_1") (pintype "passive"))
      (node (ref "C71") (pin "1") (pinfunction "-_1") (pintype "passive"))
      (node (ref "C72") (pin "1") (pinfunction "-_1") (pintype "passive"))
      (node (ref "C73") (pin "1") (pinfunction "-_1") (pintype "passive"))
      (node (ref "C74") (pin "1") (pinfunction "-_1") (pintype "passive"))
      (node (ref "C75") (pin "1") (pinfunction "-_1") (pintype "passive"))
      (node (ref "C76") (pin "1") (pinfunction "-_1") (pintype "passive"))
      (node (ref "C77") (pin "1") (pinfunction "-_1") (pintype "passive"))
      (node (ref "C78") (pin "1") (pinfunction "-_1") (pintype "passive"))
      (node (ref "C79") (pin "1") (pinfunction "-_1") (pintype "passive"))
      (node (ref "C8") (pin "1") (pinfunction "-_1") (pintype "passive"))
      (node (ref "C80") (pin "1") (pinfunction "-_1") (pintype "passive"))
      (node (ref "C81") (pin "1") (pinfunction "-_1") (pintype "passive"))
      (node (ref "C82") (pin "1") (pinfunction "-_1") (pintype "passive"))
      (node (ref "C83") (pin "1") (pinfunction "-_1") (pintype "passive"))
      (node (ref "C84") (pin "1") (pinfunction "-_1") (pintype "passive"))
      (node (ref "C85") (pin "1") (pinfunction "-_1") (pintype "passive"))
      (node (ref "C86") (pin "1") (pinfunction "-_1") (pintype "passive"))
      (node (ref "C87") (pin "1") (pinfunction "-_1") (pintype "passive"))
      (node (ref "C88") (pin "1") (pinfunction "-_1") (pintype "passive"))
      (node (ref "C89") (pin "1") (pinfunction "-_1") (pintype "passive"))
      (node (ref "C9") (pin "1") (pinfunction "-_1") (pintype "passive"))
      (node (ref "C90") (pin "1") (pinfunction "-_1") (pintype "passive"))
      (node (ref "C91") (pin "1") (pinfunction "-_1") (pintype "passive"))
      (node (ref "C92") (pin "1") (pinfunction "-_1") (pintype "passive"))
      (node (ref "C93") (pin "1") (pinfunction "-_1") (pintype "passive"))
      (node (ref "C94") (pin "1") (pinfunction "-_1") (pintype "passive"))
      (node (ref "C95") (pin "1") (pinfunction "-_1") (pintype "passive"))
      (node (ref "C96") (pin "1") (pinfunction "-_1") (pintype "passive"))
      (node (ref "C97") (pin "1") (pinfunction "-_1") (pintype "passive"))
      (node (ref "C98") (pin "1") (pinfunction "-_1") (pintype "passive"))
      (node (ref "C99") (pin "1") (pinfunction "-_1") (pintype "passive"))
      (node (ref "D9") (pin "1") (pinfunction "+_1") (pintype "passive"))
      (node (ref "Fan1") (pin "2") (pinfunction "-_2") (pintype "passive"))
      (node (ref "J1") (pin "3") (pinfunction "GND_3") (pintype "power_in"))
      (node (ref "J2") (pin "2") (pinfunction "GND_2") (pintype "power_in"))
      (node (ref "J2") (pin "3") (pinfunction "GND_3") (pintype "power_in"))
      (node (ref "J3") (pin "3") (pinfunction "GND_3") (pintype "passive"))
      (node (ref "J7") (pin "4") (pinfunction "GND_4") (pintype "passive"))
      (node (ref "LED1") (pin "3") (pinfunction "VSS_3") (pintype "passive"))
      (node (ref "LED10") (pin "3") (pinfunction "VSS_3") (pintype "passive"))
      (node (ref "LED100") (pin "3") (pinfunction "VSS_3") (pintype "passive"))
      (node (ref "LED101") (pin "3") (pinfunction "VSS_3") (pintype "passive"))
      (node (ref "LED102") (pin "3") (pinfunction "VSS_3") (pintype "passive"))
      (node (ref "LED103") (pin "3") (pinfunction "VSS_3") (pintype "passive"))
      (node (ref "LED104") (pin "3") (pinfunction "VSS_3") (pintype "passive"))
      (node (ref "LED105") (pin "3") (pinfunction "VSS_3") (pintype "passive"))
      (node (ref "LED106") (pin "3") (pinfunction "VSS_3") (pintype "passive"))
      (node (ref "LED107") (pin "3") (pinfunction "VSS_3") (pintype "passive"))
      (node (ref "LED108") (pin "3") (pinfunction "VSS_3") (pintype "passive"))
      (node (ref "LED109") (pin "3") (pinfunction "VSS_3") (pintype "passive"))
      (node (ref "LED11") (pin "3") (pinfunction "VSS_3") (pintype "passive"))
      (node (ref "LED110") (pin "3") (pinfunction "VSS_3") (pintype "passive"))
      (node (ref "LED111") (pin "3") (pinfunction "VSS_3") (pintype "passive"))
      (node (ref "LED112") (pin "3") (pinfunction "VSS_3") (pintype "passive"))
      (node (ref "LED12") (pin "3") (pinfunction "VSS_3") (pintype "passive"))
      (node (ref "LED13") (pin "3") (pinfunction "VSS_3") (pintype "passive"))
      (node (ref "LED14") (pin "3") (pinfunction "VSS_3") (pintype "passive"))
      (node (ref "LED15") (pin "3") (pinfunction "VSS_3") (pintype "passive"))
      (node (ref "LED16") (pin "3") (pinfunction "VSS_3") (pintype "passive"))
      (node (ref "LED17") (pin "3") (pinfunction "VSS_3") (pintype "passive"))
      (node (ref "LED18") (pin "3") (pinfunction "VSS_3") (pintype "passive"))
      (node (ref "LED19") (pin "3") (pinfunction "VSS_3") (pintype "passive"))
      (node (ref "LED2") (pin "3") (pinfunction "VSS_3") (pintype "passive"))
      (node (ref "LED20") (pin "3") (pinfunction "VSS_3") (pintype "passive"))
      (node (ref "LED21") (pin "3") (pinfunction "VSS_3") (pintype "passive"))
      (node (ref "LED22") (pin "3") (pinfunction "VSS_3") (pintype "passive"))
      (node (ref "LED23") (pin "3") (pinfunction "VSS_3") (pintype "passive"))
      (node (ref "LED24") (pin "3") (pinfunction "VSS_3") (pintype "passive"))
      (node (ref "LED25") (pin "3") (pinfunction "VSS_3") (pintype "passive"))
      (node (ref "LED26") (pin "3") (pinfunction "VSS_3") (pintype "passive"))
      (node (ref "LED27") (pin "3") (pinfunction "VSS_3") (pintype "passive"))
      (node (ref "LED28") (pin "3") (pinfunction "VSS_3") (pintype "passive"))
      (node (ref "LED29") (pin "3") (pinfunction "VSS_3") (pintype "passive"))
      (node (ref "LED3") (pin "3") (pinfunction "VSS_3") (pintype "passive"))
      (node (ref "LED30") (pin "3") (pinfunction "VSS_3") (pintype "passive"))
      (node (ref "LED31") (pin "3") (pinfunction "VSS_3") (pintype "passive"))
      (node (ref "LED32") (pin "3") (pinfunction "VSS_3") (pintype "passive"))
      (node (ref "LED33") (pin "3") (pinfunction "VSS_3") (pintype "passive"))
      (node (ref "LED34") (pin "3") (pinfunction "VSS_3") (pintype "passive"))
      (node (ref "LED35") (pin "3") (pinfunction "VSS_3") (pintype "passive"))
      (node (ref "LED36") (pin "3") (pinfunction "VSS_3") (pintype "passive"))
      (node (ref "LED37") (pin "3") (pinfunction "VSS_3") (pintype "passive"))
      (node (ref "LED38") (pin "3") (pinfunction "VSS_3") (pintype "passive"))
      (node (ref "LED39") (pin "3") (pinfunction "VSS_3") (pintype "passive"))
      (node (ref "LED4") (pin "3") (pinfunction "VSS_3") (pintype "passive"))
      (node (ref "LED40") (pin "3") (pinfunction "VSS_3") (pintype "passive"))
      (node (ref "LED41") (pin "3") (pinfunction "VSS_3") (pintype "passive"))
      (node (ref "LED42") (pin "3") (pinfunction "VSS_3") (pintype "passive"))
      (node (ref "LED43") (pin "3") (pinfunction "VSS_3") (pintype "passive"))
      (node (ref "LED44") (pin "3") (pinfunction "VSS_3") (pintype "passive"))
      (node (ref "LED45") (pin "3") (pinfunction "VSS_3") (pintype "passive"))
      (node (ref "LED46") (pin "3") (pinfunction "VSS_3") (pintype "passive"))
      (node (ref "LED47") (pin "3") (pinfunction "VSS_3") (pintype "passive"))
      (node (ref "LED48") (pin "3") (pinfunction "VSS_3") (pintype "passive"))
      (node (ref "LED49") (pin "3") (pinfunction "VSS_3") (pintype "passive"))
      (node (ref "LED5") (pin "3") (pinfunction "VSS_3") (pintype "passive"))
      (node (ref "LED50") (pin "3") (pinfunction "VSS_3") (pintype "passive"))
      (node (ref "LED51") (pin "3") (pinfunction "VSS_3") (pintype "passive"))
      (node (ref "LED52") (pin "3") (pinfunction "VSS_3") (pintype "passive"))
      (node (ref "LED53") (pin "3") (pinfunction "VSS_3") (pintype "passive"))
      (node (ref "LED54") (pin "3") (pinfunction "VSS_3") (pintype "passive"))
      (node (ref "LED55") (pin "3") (pinfunction "VSS_3") (pintype "passive"))
      (node (ref "LED56") (pin "3") (pinfunction "VSS_3") (pintype "passive"))
      (node (ref "LED57") (pin "3") (pinfunction "VSS_3") (pintype "passive"))
      (node (ref "LED58") (pin "3") (pinfunction "VSS_3") (pintype "passive"))
      (node (ref "LED59") (pin "3") (pinfunction "VSS_3") (pintype "passive"))
      (node (ref "LED6") (pin "3") (pinfunction "VSS_3") (pintype "passive"))
      (node (ref "LED60") (pin "3") (pinfunction "VSS_3") (pintype "passive"))
      (node (ref "LED61") (pin "3") (pinfunction "VSS_3") (pintype "passive"))
      (node (ref "LED62") (pin "3") (pinfunction "VSS_3") (pintype "passive"))
      (node (ref "LED63") (pin "3") (pinfunction "VSS_3") (pintype "passive"))
      (node (ref "LED64") (pin "3") (pinfunction "VSS_3") (pintype "passive"))
      (node (ref "LED65") (pin "3") (pinfunction "VSS_3") (pintype "passive"))
      (node (ref "LED66") (pin "3") (pinfunction "VSS_3") (pintype "passive"))
      (node (ref "LED67") (pin "3") (pinfunction "VSS_3") (pintype "passive"))
      (node (ref "LED68") (pin "3") (pinfunction "VSS_3") (pintype "passive"))
      (node (ref "LED69") (pin "3") (pinfunction "VSS_3") (pintype "passive"))
      (node (ref "LED7") (pin "3") (pinfunction "VSS_3") (pintype "passive"))
      (node (ref "LED70") (pin "3") (pinfunction "VSS_3") (pintype "passive"))
      (node (ref "LED71") (pin "3") (pinfunction "VSS_3") (pintype "passive"))
      (node (ref "LED72") (pin "3") (pinfunction "VSS_3") (pintype "passive"))
      (node (ref "LED73") (pin "3") (pinfunction "VSS_3") (pintype "passive"))
      (node (ref "LED74") (pin "3") (pinfunction "VSS_3") (pintype "passive"))
      (node (ref "LED75") (pin "3") (pinfunction "VSS_3") (pintype "passive"))
      (node (ref "LED76") (pin "3") (pinfunction "VSS_3") (pintype "passive"))
      (node (ref "LED77") (pin "3") (pinfunction "VSS_3") (pintype "passive"))
      (node (ref "LED78") (pin "3") (pinfunction "VSS_3") (pintype "passive"))
      (node (ref "LED79") (pin "3") (pinfunction "VSS_3") (pintype "passive"))
      (node (ref "LED8") (pin "3") (pinfunction "VSS_3") (pintype "passive"))
      (node (ref "LED80") (pin "3") (pinfunction "VSS_3") (pintype "passive"))
      (node (ref "LED81") (pin "3") (pinfunction "VSS_3") (pintype "passive"))
      (node (ref "LED82") (pin "3") (pinfunction "VSS_3") (pintype "passive"))
      (node (ref "LED83") (pin "3") (pinfunction "VSS_3") (pintype "passive"))
      (node (ref "LED84") (pin "3") (pinfunction "VSS_3") (pintype "passive"))
      (node (ref "LED85") (pin "3") (pinfunction "VSS_3") (pintype "passive"))
      (node (ref "LED86") (pin "3") (pinfunction "VSS_3") (pintype "passive"))
      (node (ref "LED87") (pin "3") (pinfunction "VSS_3") (pintype "passive"))
      (node (ref "LED88") (pin "3") (pinfunction "VSS_3") (pintype "passive"))
      (node (ref "LED89") (pin "3") (pinfunction "VSS_3") (pintype "passive"))
      (node (ref "LED9") (pin "3") (pinfunction "VSS_3") (pintype "passive"))
      (node (ref "LED90") (pin "3") (pinfunction "VSS_3") (pintype "passive"))
      (node (ref "LED91") (pin "3") (pinfunction "VSS_3") (pintype "passive"))
      (node (ref "LED92") (pin "3") (pinfunction "VSS_3") (pintype "passive"))
      (node (ref "LED93") (pin "3") (pinfunction "VSS_3") (pintype "passive"))
      (node (ref "LED94") (pin "3") (pinfunction "VSS_3") (pintype "passive"))
      (node (ref "LED95") (pin "3") (pinfunction "VSS_3") (pintype "passive"))
      (node (ref "LED96") (pin "3") (pinfunction "VSS_3") (pintype "passive"))
      (node (ref "LED97") (pin "3") (pinfunction "VSS_3") (pintype "passive"))
      (node (ref "LED98") (pin "3") (pinfunction "VSS_3") (pintype "passive"))
      (node (ref "LED99") (pin "3") (pinfunction "VSS_3") (pintype "passive"))
      (node (ref "R6") (pin "1") (pinfunction "1_1") (pintype "passive"))
      (node (ref "R7") (pin "1") (pinfunction "1_1") (pintype "passive"))
      (node (ref "Relay1") (pin "2") (pinfunction "Coli_B_2") (pintype "passive"))
      (node (ref "Screen") (pin "2") (pinfunction "GND_2") (pintype "passive"))
      (node (ref "T1") (pin "11") (pinfunction "GND_11") (pintype "passive"))
      (node (ref "T1") (pin "2") (pinfunction "GND_2") (pintype "passive"))
      (node (ref "T1") (pin "5") (pinfunction "GND_5") (pintype "passive"))
      (node (ref "T1") (pin "8") (pinfunction "GND_8") (pintype "passive"))
      (node (ref "T2") (pin "11") (pinfunction "GND_11") (pintype "passive"))
      (node (ref "T2") (pin "2") (pinfunction "GND_2") (pintype "passive"))
      (node (ref "T2") (pin "5") (pinfunction "GND_5") (pintype "passive"))
      (node (ref "T2") (pin "8") (pinfunction "GND_8") (pintype "passive"))
      (node (ref "cp1") (pin "29") (pinfunction "GND_29") (pintype "passive"))
      (node (ref "cp1") (pin "3") (pinfunction "GND_3") (pintype "passive"))
      (node (ref "esp1") (pin "1") (pinfunction "GND_1") (pintype "power_in"))
      (node (ref "esp1") (pin "18") (pinfunction "GND_18") (pintype "power_in"))
      (node (ref "esp1") (pin "36") (pinfunction "GND_36") (pintype "power_in"))
      (node (ref "esp1") (pin "7") (pinfunction "GND_7") (pintype "power_in"))
      (node (ref "esp1") (pin "8") (pinfunction "GND_8") (pintype "power_in"))
      (node (ref "usb1") (pin "1") (pinfunction "GND_1") (pintype "power_in"))
    )
    (net (code "33") (name "Net-(C66-+)") (class "Default")
      (node (ref "C66") (pin "2") (pinfunction "+_2") (pintype "passive"))
      (node (ref "C67") (pin "2") (pinfunction "+_2") (pintype "passive"))
      (node (ref "R5") (pin "1") (pinfunction "1_1") (pintype "passive"))
      (node (ref "cp1") (pin "6") (pinfunction "VDD_6") (pintype "passive"))
    )
    (net (code "34") (name "Net-(D1-Pad1)") (class "Default")
      (node (ref "D1") (pin "1") (pinfunction "1_1") (pintype "passive"))
      (node (ref "T1") (pin "9") (pinfunction "OUT_9") (pintype "passive"))
    )
    (net (code "35") (name "Net-(D2-Pad1)") (class "Default")
      (node (ref "D2") (pin "1") (pinfunction "1_1") (pintype "passive"))
      (node (ref "T1") (pin "12") (pinfunction "OUT_12") (pintype "passive"))
    )
    (net (code "36") (name "Net-(D3-Pad1)") (class "Default")
      (node (ref "D3") (pin "1") (pinfunction "1_1") (pintype "passive"))
      (node (ref "T1") (pin "3") (pinfunction "OUT_3") (pintype "passive"))
    )
    (net (code "37") (name "Net-(D4-Pad1)") (class "Default")
      (node (ref "D4") (pin "1") (pinfunction "1_1") (pintype "passive"))
      (node (ref "T1") (pin "6") (pinfunction "OUT_6") (pintype "passive"))
    )
    (net (code "38") (name "Net-(D5-Pad1)") (class "Default")
      (node (ref "D5") (pin "1") (pinfunction "1_1") (pintype "passive"))
      (node (ref "T2") (pin "9") (pinfunction "OUT_9") (pintype "passive"))
    )
    (net (code "39") (name "Net-(D6-Pad1)") (class "Default")
      (node (ref "D6") (pin "1") (pinfunction "1_1") (pintype "passive"))
      (node (ref "T2") (pin "12") (pinfunction "OUT_12") (pintype "passive"))
    )
    (net (code "40") (name "Net-(D7-Pad1)") (class "Default")
      (node (ref "D7") (pin "1") (pinfunction "1_1") (pintype "passive"))
      (node (ref "T2") (pin "3") (pinfunction "OUT_3") (pintype "passive"))
    )
    (net (code "41") (name "Net-(D8-Pad1)") (class "Default")
      (node (ref "D8") (pin "1") (pinfunction "1_1") (pintype "passive"))
      (node (ref "T2") (pin "6") (pinfunction "OUT_6") (pintype "passive"))
    )
    (net (code "42") (name "Net-(D11-Pad1)") (class "Default")
      (node (ref "D11") (pin "1") (pinfunction "1_1") (pintype "passive"))
      (node (ref "R7") (pin "2") (pinfunction "2_2") (pintype "passive"))
    )
    (net (code "43") (name "Net-(D11-Pad2)") (class "Default")
      (node (ref "D11") (pin "2") (pinfunction "2_2") (pintype "passive"))
      (node (ref "esp1") (pin "4") (pinfunction "3v3_4") (pintype "power_in"))
    )
    (net (code "44") (name "Net-(Fan1-+)") (class "Default")
      (node (ref "Fan1") (pin "1") (pinfunction "+_1") (pintype "passive"))
      (node (ref "irl") (pin "3") (pinfunction "Source_3") (pintype "passive"))
    )
    (net (code "45") (name "Net-(LED1-DOUT)") (class "Default")
      (node (ref "LED1") (pin "2") (pinfunction "DOUT_2") (pintype "passive"))
      (node (ref "LED2") (pin "4") (pinfunction "DIN_4") (pintype "passive"))
    )
    (net (code "46") (name "Net-(LED2-DOUT)") (class "Default")
      (node (ref "LED2") (pin "2") (pinfunction "DOUT_2") (pintype "passive"))
      (node (ref "LED3") (pin "4") (pinfunction "DIN_4") (pintype "passive"))
    )
    (net (code "47") (name "Net-(LED3-DOUT)") (class "Default")
      (node (ref "LED3") (pin "2") (pinfunction "DOUT_2") (pintype "passive"))
      (node (ref "LED4") (pin "4") (pinfunction "DIN_4") (pintype "passive"))
    )
    (net (code "48") (name "Net-(LED4-DOUT)") (class "Default")
      (node (ref "LED4") (pin "2") (pinfunction "DOUT_2") (pintype "passive"))
      (node (ref "LED5") (pin "4") (pinfunction "DIN_4") (pintype "passive"))
    )
    (net (code "49") (name "Net-(LED5-DOUT)") (class "Default")
      (node (ref "LED5") (pin "2") (pinfunction "DOUT_2") (pintype "passive"))
      (node (ref "LED6") (pin "4") (pinfunction "DIN_4") (pintype "passive"))
    )
    (net (code "50") (name "Net-(LED6-DOUT)") (class "Default")
      (node (ref "LED6") (pin "2") (pinfunction "DOUT_2") (pintype "passive"))
      (node (ref "LED7") (pin "4") (pinfunction "DIN_4") (pintype "passive"))
    )
    (net (code "51") (name "Net-(LED7-DOUT)") (class "Default")
      (node (ref "LED7") (pin "2") (pinfunction "DOUT_2") (pintype "passive"))
      (node (ref "LED8") (pin "4") (pinfunction "DIN_4") (pintype "passive"))
    )
    (net (code "52") (name "Net-(LED8-DOUT)") (class "Default")
      (node (ref "LED8") (pin "2") (pinfunction "DOUT_2") (pintype "passive"))
      (node (ref "LED9") (pin "4") (pinfunction "DIN_4") (pintype "passive"))
    )
    (net (code "53") (name "Net-(LED10-DIN)") (class "Default")
      (node (ref "LED10") (pin "4") (pinfunction "DIN_4") (pintype "passive"))
      (node (ref "LED9") (pin "2") (pinfunction "DOUT_2") (pintype "passive"))
    )
    (net (code "54") (name "Net-(LED10-DOUT)") (class "Default")
      (node (ref "LED10") (pin "2") (pinfunction "DOUT_2") (pintype "passive"))
      (node (ref "LED11") (pin "4") (pinfunction "DIN_4") (pintype "passive"))
    )
    (net (code "55") (name "Net-(LED11-DOUT)") (class "Default")
      (node (ref "LED11") (pin "2") (pinfunction "DOUT_2") (pintype "passive"))
      (node (ref "LED12") (pin "4") (pinfunction "DIN_4") (pintype "passive"))
    )
    (net (code "56") (name "Net-(LED12-DOUT)") (class "Default")
      (node (ref "LED12") (pin "2") (pinfunction "DOUT_2") (pintype "passive"))
      (node (ref "LED13") (pin "4") (pinfunction "DIN_4") (pintype "passive"))
    )
    (net (code "57") (name "Net-(LED13-DOUT)") (class "Default")
      (node (ref "LED13") (pin "2") (pinfunction "DOUT_2") (pintype "passive"))
      (node (ref "LED14") (pin "4") (pinfunction "DIN_4") (pintype "passive"))
    )
    (net (code "58") (name "Net-(LED14-DOUT)") (class "Default")
      (node (ref "LED14") (pin "2") (pinfunction "DOUT_2") (pintype "passive"))
      (node (ref "LED15") (pin "4") (pinfunction "DIN_4") (pintype "passive"))
    )
    (net (code "59") (name "Net-(LED15-DOUT)") (class "Default")
      (node (ref "LED15") (pin "2") (pinfunction "DOUT_2") (pintype "passive"))
      (node (ref "LED16") (pin "4") (pinfunction "DIN_4") (pintype "passive"))
    )
    (net (code "60") (name "Net-(LED16-DOUT)") (class "Default")
      (node (ref "LED16") (pin "2") (pinfunction "DOUT_2") (pintype "passive"))
      (node (ref "LED17") (pin "4") (pinfunction "DIN_4") (pintype "passive"))
    )
    (net (code "61") (name "Net-(LED17-DOUT)") (class "Default")
      (node (ref "LED17") (pin "2") (pinfunction "DOUT_2") (pintype "passive"))
      (node (ref "LED18") (pin "4") (pinfunction "DIN_4") (pintype "passive"))
    )
    (net (code "62") (name "Net-(LED18-DOUT)") (class "Default")
      (node (ref "LED18") (pin "2") (pinfunction "DOUT_2") (pintype "passive"))
      (node (ref "LED19") (pin "4") (pinfunction "DIN_4") (pintype "passive"))
    )
    (net (code "63") (name "Net-(LED19-DOUT)") (class "Default")
      (node (ref "LED19") (pin "2") (pinfunction "DOUT_2") (pintype "passive"))
      (node (ref "LED20") (pin "4") (pinfunction "DIN_4") (pintype "passive"))
    )
    (net (code "64") (name "Net-(LED20-DOUT)") (class "Default")
      (node (ref "LED20") (pin "2") (pinfunction "DOUT_2") (pintype "passive"))
      (node (ref "LED21") (pin "4") (pinfunction "DIN_4") (pintype "passive"))
    )
    (net (code "65") (name "Net-(LED21-DOUT)") (class "Default")
      (node (ref "LED21") (pin "2") (pinfunction "DOUT_2") (pintype "passive"))
      (node (ref "LED22") (pin "4") (pinfunction "DIN_4") (pintype "passive"))
    )
    (net (code "66") (name "Net-(LED22-DOUT)") (class "Default")
      (node (ref "LED22") (pin "2") (pinfunction "DOUT_2") (pintype "passive"))
      (node (ref "LED23") (pin "4") (pinfunction "DIN_4") (pintype "passive"))
    )
    (net (code "67") (name "Net-(LED23-DOUT)") (class "Default")
      (node (ref "LED23") (pin "2") (pinfunction "DOUT_2") (pintype "passive"))
      (node (ref "LED24") (pin "4") (pinfunction "DIN_4") (pintype "passive"))
    )
    (net (code "68") (name "Net-(LED24-DOUT)") (class "Default")
      (node (ref "LED24") (pin "2") (pinfunction "DOUT_2") (pintype "passive"))
      (node (ref "LED25") (pin "4") (pinfunction "DIN_4") (pintype "passive"))
    )
    (net (code "69") (name "Net-(LED25-DOUT)") (class "Default")
      (node (ref "LED25") (pin "2") (pinfunction "DOUT_2") (pintype "passive"))
      (node (ref "LED26") (pin "4") (pinfunction "DIN_4") (pintype "passive"))
    )
    (net (code "70") (name "Net-(LED26-DOUT)") (class "Default")
      (node (ref "LED26") (pin "2") (pinfunction "DOUT_2") (pintype "passive"))
      (node (ref "LED27") (pin "4") (pinfunction "DIN_4") (pintype "passive"))
    )
    (net (code "71") (name "Net-(LED27-DOUT)") (class "Default")
      (node (ref "LED27") (pin "2") (pinfunction "DOUT_2") (pintype "passive"))
      (node (ref "LED28") (pin "4") (pinfunction "DIN_4") (pintype "passive"))
    )
    (net (code "72") (name "Net-(LED28-DOUT)") (class "Default")
      (node (ref "LED28") (pin "2") (pinfunction "DOUT_2") (pintype "passive"))
      (node (ref "LED29") (pin "4") (pinfunction "DIN_4") (pintype "passive"))
    )
    (net (code "73") (name "Net-(LED29-DOUT)") (class "Default")
      (node (ref "LED29") (pin "2") (pinfunction "DOUT_2") (pintype "passive"))
      (node (ref "LED30") (pin "4") (pinfunction "DIN_4") (pintype "passive"))
    )
    (net (code "74") (name "Net-(LED30-DOUT)") (class "Default")
      (node (ref "LED30") (pin "2") (pinfunction "DOUT_2") (pintype "passive"))
      (node (ref "LED31") (pin "4") (pinfunction "DIN_4") (pintype "passive"))
    )
    (net (code "75") (name "Net-(LED31-DOUT)") (class "Default")
      (node (ref "LED31") (pin "2") (pinfunction "DOUT_2") (pintype "passive"))
      (node (ref "LED32") (pin "4") (pinfunction "DIN_4") (pintype "passive"))
    )
    (net (code "76") (name "Net-(LED32-DOUT)") (class "Default")
      (node (ref "LED32") (pin "2") (pinfunction "DOUT_2") (pintype "passive"))
      (node (ref "LED33") (pin "4") (pinfunction "DIN_4") (pintype "passive"))
    )
    (net (code "77") (name "Net-(LED33-DOUT)") (class "Default")
      (node (ref "LED33") (pin "2") (pinfunction "DOUT_2") (pintype "passive"))
      (node (ref "LED34") (pin "4") (pinfunction "DIN_4") (pintype "passive"))
    )
    (net (code "78") (name "Net-(LED34-DOUT)") (class "Default")
      (node (ref "LED34") (pin "2") (pinfunction "DOUT_2") (pintype "passive"))
      (node (ref "LED35") (pin "4") (pinfunction "DIN_4") (pintype "passive"))
    )
    (net (code "79") (name "Net-(LED35-DOUT)") (class "Default")
      (node (ref "LED35") (pin "2") (pinfunction "DOUT_2") (pintype "passive"))
      (node (ref "LED36") (pin "4") (pinfunction "DIN_4") (pintype "passive"))
    )
    (net (code "80") (name "Net-(LED36-DOUT)") (class "Default")
      (node (ref "LED36") (pin "2") (pinfunction "DOUT_2") (pintype "passive"))
      (node (ref "LED37") (pin "4") (pinfunction "DIN_4") (pintype "passive"))
    )
    (net (code "81") (name "Net-(LED37-DOUT)") (class "Default")
      (node (ref "LED37") (pin "2") (pinfunction "DOUT_2") (pintype "passive"))
      (node (ref "LED38") (pin "4") (pinfunction "DIN_4") (pintype "passive"))
    )
    (net (code "82") (name "Net-(LED38-DOUT)") (class "Default")
      (node (ref "LED38") (pin "2") (pinfunction "DOUT_2") (pintype "passive"))
      (node (ref "LED39") (pin "4") (pinfunction "DIN_4") (pintype "passive"))
    )
    (net (code "83") (name "Net-(LED39-DOUT)") (class "Default")
      (node (ref "LED39") (pin "2") (pinfunction "DOUT_2") (pintype "passive"))
      (node (ref "LED40") (pin "4") (pinfunction "DIN_4") (pintype "passive"))
    )
    (net (code "84") (name "Net-(LED40-DOUT)") (class "Default")
      (node (ref "LED40") (pin "2") (pinfunction "DOUT_2") (pintype "passive"))
      (node (ref "LED41") (pin "4") (pinfunction "DIN_4") (pintype "passive"))
    )
    (net (code "85") (name "Net-(LED41-DOUT)") (class "Default")
      (node (ref "LED41") (pin "2") (pinfunction "DOUT_2") (pintype "passive"))
      (node (ref "LED42") (pin "4") (pinfunction "DIN_4") (pintype "passive"))
    )
    (net (code "86") (name "Net-(LED42-DOUT)") (class "Default")
      (node (ref "LED42") (pin "2") (pinfunction "DOUT_2") (pintype "passive"))
      (node (ref "LED43") (pin "4") (pinfunction "DIN_4") (pintype "passive"))
    )
    (net (code "87") (name "Net-(LED43-DOUT)") (class "Default")
      (node (ref "LED43") (pin "2") (pinfunction "DOUT_2") (pintype "passive"))
      (node (ref "LED44") (pin "4") (pinfunction "DIN_4") (pintype "passive"))
    )
    (net (code "88") (name "Net-(LED44-DOUT)") (class "Default")
      (node (ref "LED44") (pin "2") (pinfunction "DOUT_2") (pintype "passive"))
      (node (ref "LED45") (pin "4") (pinfunction "DIN_4") (pintype "passive"))
    )
    (net (code "89") (name "Net-(LED45-DOUT)") (class "Default")
      (node (ref "LED45") (pin "2") (pinfunction "DOUT_2") (pintype "passive"))
      (node (ref "LED46") (pin "4") (pinfunction "DIN_4") (pintype "passive"))
    )
    (net (code "90") (name "Net-(LED46-DOUT)") (class "Default")
      (node (ref "LED46") (pin "2") (pinfunction "DOUT_2") (pintype "passive"))
      (node (ref "LED47") (pin "4") (pinfunction "DIN_4") (pintype "passive"))
    )
    (net (code "91") (name "Net-(LED47-DOUT)") (class "Default")
      (node (ref "LED47") (pin "2") (pinfunction "DOUT_2") (pintype "passive"))
      (node (ref "LED48") (pin "4") (pinfunction "DIN_4") (pintype "passive"))
    )
    (net (code "92") (name "Net-(LED48-DOUT)") (class "Default")
      (node (ref "LED48") (pin "2") (pinfunction "DOUT_2") (pintype "passive"))
      (node (ref "LED49") (pin "4") (pinfunction "DIN_4") (pintype "passive"))
    )
    (net (code "93") (name "Net-(LED49-DOUT)") (class "Default")
      (node (ref "LED49") (pin "2") (pinfunction "DOUT_2") (pintype "passive"))
      (node (ref "LED50") (pin "4") (pinfunction "DIN_4") (pintype "passive"))
    )
    (net (code "94") (name "Net-(LED50-DOUT)") (class "Default")
      (node (ref "LED50") (pin "2") (pinfunction "DOUT_2") (pintype "passive"))
      (node (ref "LED51") (pin "4") (pinfunction "DIN_4") (pintype "passive"))
    )
    (net (code "95") (name "Net-(LED51-DOUT)") (class "Default")
      (node (ref "LED51") (pin "2") (pinfunction "DOUT_2") (pintype "passive"))
      (node (ref "LED52") (pin "4") (pinfunction "DIN_4") (pintype "passive"))
    )
    (net (code "96") (name "Net-(LED52-DOUT)") (class "Default")
      (node (ref "LED52") (pin "2") (pinfunction "DOUT_2") (pintype "passive"))
      (node (ref "LED53") (pin "4") (pinfunction "DIN_4") (pintype "passive"))
    )
    (net (code "97") (name "Net-(LED53-DOUT)") (class "Default")
      (node (ref "LED53") (pin "2") (pinfunction "DOUT_2") (pintype "passive"))
      (node (ref "LED54") (pin "4") (pinfunction "DIN_4") (pintype "passive"))
    )
    (net (code "98") (name "Net-(LED54-DOUT)") (class "Default")
      (node (ref "LED54") (pin "2") (pinfunction "DOUT_2") (pintype "passive"))
      (node (ref "LED55") (pin "4") (pinfunction "DIN_4") (pintype "passive"))
    )
    (net (code "99") (name "Net-(LED55-DOUT)") (class "Default")
      (node (ref "LED55") (pin "2") (pinfunction "DOUT_2") (pintype "passive"))
      (node (ref "LED56") (pin "4") (pinfunction "DIN_4") (pintype "passive"))
    )
    (net (code "100") (name "Net-(LED56-DOUT)") (class "Default")
      (node (ref "LED56") (pin "2") (pinfunction "DOUT_2") (pintype "passive"))
      (node (ref "LED57") (pin "4") (pinfunction "DIN_4") (pintype "passive"))
    )
    (net (code "101") (name "Net-(LED57-DOUT)") (class "Default")
      (node (ref "LED57") (pin "2") (pinfunction "DOUT_2") (pintype "passive"))
      (node (ref "LED58") (pin "4") (pinfunction "DIN_4") (pintype "passive"))
    )
    (net (code "102") (name "Net-(LED58-DOUT)") (class "Default")
      (node (ref "LED58") (pin "2") (pinfunction "DOUT_2") (pintype "passive"))
      (node (ref "LED59") (pin "4") (pinfunction "DIN_4") (pintype "passive"))
    )
    (net (code "103") (name "Net-(LED59-DOUT)") (class "Default")
      (node (ref "LED59") (pin "2") (pinfunction "DOUT_2") (pintype "passive"))
      (node (ref "LED60") (pin "4") (pinfunction "DIN_4") (pintype "passive"))
    )
    (net (code "104") (name "Net-(LED60-DOUT)") (class "Default")
      (node (ref "LED60") (pin "2") (pinfunction "DOUT_2") (pintype "passive"))
      (node (ref "LED61") (pin "4") (pinfunction "DIN_4") (pintype "passive"))
    )
    (net (code "105") (name "Net-(LED61-DOUT)") (class "Default")
      (node (ref "LED61") (pin "2") (pinfunction "DOUT_2") (pintype "passive"))
      (node (ref "LED62") (pin "4") (pinfunction "DIN_4") (pintype "passive"))
    )
    (net (code "106") (name "Net-(LED62-DOUT)") (class "Default")
      (node (ref "LED62") (pin "2") (pinfunction "DOUT_2") (pintype "passive"))
      (node (ref "LED63") (pin "4") (pinfunction "DIN_4") (pintype "passive"))
    )
    (net (code "107") (name "Net-(LED63-DOUT)") (class "Default")
      (node (ref "LED63") (pin "2") (pinfunction "DOUT_2") (pintype "passive"))
      (node (ref "LED64") (pin "4") (pinfunction "DIN_4") (pintype "passive"))
    )
    (net (code "108") (name "Net-(LED64-DOUT)") (class "Default")
      (node (ref "LED64") (pin "2") (pinfunction "DOUT_2") (pintype "passive"))
      (node (ref "LED65") (pin "4") (pinfunction "DIN_4") (pintype "passive"))
    )
    (net (code "109") (name "Net-(LED65-DOUT)") (class "Default")
      (node (ref "LED65") (pin "2") (pinfunction "DOUT_2") (pintype "passive"))
      (node (ref "LED66") (pin "4") (pinfunction "DIN_4") (pintype "passive"))
    )
    (net (code "110") (name "Net-(LED66-DOUT)") (class "Default")
      (node (ref "LED66") (pin "2") (pinfunction "DOUT_2") (pintype "passive"))
      (node (ref "LED67") (pin "4") (pinfunction "DIN_4") (pintype "passive"))
    )
    (net (code "111") (name "Net-(LED67-DOUT)") (class "Default")
      (node (ref "LED67") (pin "2") (pinfunction "DOUT_2") (pintype "passive"))
      (node (ref "LED68") (pin "4") (pinfunction "DIN_4") (pintype "passive"))
    )
    (net (code "112") (name "Net-(LED68-DOUT)") (class "Default")
      (node (ref "LED68") (pin "2") (pinfunction "DOUT_2") (pintype "passive"))
      (node (ref "LED69") (pin "4") (pinfunction "DIN_4") (pintype "passive"))
    )
    (net (code "113") (name "Net-(LED69-DOUT)") (class "Default")
      (node (ref "LED69") (pin "2") (pinfunction "DOUT_2") (pintype "passive"))
      (node (ref "LED70") (pin "4") (pinfunction "DIN_4") (pintype "passive"))
    )
    (net (code "114") (name "Net-(LED70-DOUT)") (class "Default")
      (node (ref "LED70") (pin "2") (pinfunction "DOUT_2") (pintype "passive"))
      (node (ref "LED71") (pin "4") (pinfunction "DIN_4") (pintype "passive"))
    )
    (net (code "115") (name "Net-(LED71-DOUT)") (class "Default")
      (node (ref "LED71") (pin "2") (pinfunction "DOUT_2") (pintype "passive"))
      (node (ref "LED72") (pin "4") (pinfunction "DIN_4") (pintype "passive"))
    )
    (net (code "116") (name "Net-(LED72-DOUT)") (class "Default")
      (node (ref "LED72") (pin "2") (pinfunction "DOUT_2") (pintype "passive"))
      (node (ref "LED73") (pin "4") (pinfunction "DIN_4") (pintype "passive"))
    )
    (net (code "117") (name "Net-(LED73-DOUT)") (class "Default")
      (node (ref "LED73") (pin "2") (pinfunction "DOUT_2") (pintype "passive"))
      (node (ref "LED74") (pin "4") (pinfunction "DIN_4") (pintype "passive"))
    )
    (net (code "118") (name "Net-(LED74-DOUT)") (class "Default")
      (node (ref "LED74") (pin "2") (pinfunction "DOUT_2") (pintype "passive"))
      (node (ref "LED75") (pin "4") (pinfunction "DIN_4") (pintype "passive"))
    )
    (net (code "119") (name "Net-(LED75-DOUT)") (class "Default")
      (node (ref "LED75") (pin "2") (pinfunction "DOUT_2") (pintype "passive"))
      (node (ref "LED76") (pin "4") (pinfunction "DIN_4") (pintype "passive"))
    )
    (net (code "120") (name "Net-(LED76-DOUT)") (class "Default")
      (node (ref "LED76") (pin "2") (pinfunction "DOUT_2") (pintype "passive"))
      (node (ref "LED77") (pin "4") (pinfunction "DIN_4") (pintype "passive"))
    )
    (net (code "121") (name "Net-(LED77-DOUT)") (class "Default")
      (node (ref "LED77") (pin "2") (pinfunction "DOUT_2") (pintype "passive"))
      (node (ref "LED78") (pin "4") (pinfunction "DIN_4") (pintype "passive"))
    )
    (net (code "122") (name "Net-(LED78-DOUT)") (class "Default")
      (node (ref "LED78") (pin "2") (pinfunction "DOUT_2") (pintype "passive"))
      (node (ref "LED79") (pin "4") (pinfunction "DIN_4") (pintype "passive"))
    )
    (net (code "123") (name "Net-(LED79-DOUT)") (class "Default")
      (node (ref "LED79") (pin "2") (pinfunction "DOUT_2") (pintype "passive"))
      (node (ref "LED80") (pin "4") (pinfunction "DIN_4") (pintype "passive"))
    )
    (net (code "124") (name "Net-(LED80-DOUT)") (class "Default")
      (node (ref "LED80") (pin "2") (pinfunction "DOUT_2") (pintype "passive"))
      (node (ref "LED81") (pin "4") (pinfunction "DIN_4") (pintype "passive"))
    )
    (net (code "125") (name "Net-(LED81-DOUT)") (class "Default")
      (node (ref "LED81") (pin "2") (pinfunction "DOUT_2") (pintype "passive"))
      (node (ref "LED82") (pin "4") (pinfunction "DIN_4") (pintype "passive"))
    )
    (net (code "126") (name "Net-(LED82-DOUT)") (class "Default")
      (node (ref "LED82") (pin "2") (pinfunction "DOUT_2") (pintype "passive"))
      (node (ref "LED83") (pin "4") (pinfunction "DIN_4") (pintype "passive"))
    )
    (net (code "127") (name "Net-(LED83-DOUT)") (class "Default")
      (node (ref "LED83") (pin "2") (pinfunction "DOUT_2") (pintype "passive"))
      (node (ref "LED84") (pin "4") (pinfunction "DIN_4") (pintype "passive"))
    )
    (net (code "128") (name "Net-(LED84-DOUT)") (class "Default")
      (node (ref "LED84") (pin "2") (pinfunction "DOUT_2") (pintype "passive"))
      (node (ref "LED85") (pin "4") (pinfunction "DIN_4") (pintype "passive"))
    )
    (net (code "129") (name "Net-(LED85-DOUT)") (class "Default")
      (node (ref "LED85") (pin "2") (pinfunction "DOUT_2") (pintype "passive"))
      (node (ref "LED86") (pin "4") (pinfunction "DIN_4") (pintype "passive"))
    )
    (net (code "130") (name "Net-(LED86-DOUT)") (class "Default")
      (node (ref "LED86") (pin "2") (pinfunction "DOUT_2") (pintype "passive"))
      (node (ref "LED87") (pin "4") (pinfunction "DIN_4") (pintype "passive"))
    )
    (net (code "131") (name "Net-(LED87-DOUT)") (class "Default")
      (node (ref "LED87") (pin "2") (pinfunction "DOUT_2") (pintype "passive"))
      (node (ref "LED88") (pin "4") (pinfunction "DIN_4") (pintype "passive"))
    )
    (net (code "132") (name "Net-(LED88-DOUT)") (class "Default")
      (node (ref "LED88") (pin "2") (pinfunction "DOUT_2") (pintype "passive"))
      (node (ref "LED89") (pin "4") (pinfunction "DIN_4") (pintype "passive"))
    )
    (net (code "133") (name "Net-(LED89-DOUT)") (class "Default")
      (node (ref "LED89") (pin "2") (pinfunction "DOUT_2") (pintype "passive"))
      (node (ref "LED90") (pin "4") (pinfunction "DIN_4") (pintype "passive"))
    )
    (net (code "134") (name "Net-(LED90-DOUT)") (class "Default")
      (node (ref "LED90") (pin "2") (pinfunction "DOUT_2") (pintype "passive"))
      (node (ref "LED91") (pin "4") (pinfunction "DIN_4") (pintype "passive"))
    )
    (net (code "135") (name "Net-(LED91-DOUT)") (class "Default")
      (node (ref "LED91") (pin "2") (pinfunction "DOUT_2") (pintype "passive"))
      (node (ref "LED92") (pin "4") (pinfunction "DIN_4") (pintype "passive"))
    )
    (net (code "136") (name "Net-(LED92-DOUT)") (class "Default")
      (node (ref "LED92") (pin "2") (pinfunction "DOUT_2") (pintype "passive"))
      (node (ref "LED93") (pin "4") (pinfunction "DIN_4") (pintype "passive"))
    )
    (net (code "137") (name "Net-(LED93-DOUT)") (class "Default")
      (node (ref "LED93") (pin "2") (pinfunction "DOUT_2") (pintype "passive"))
      (node (ref "LED94") (pin "4") (pinfunction "DIN_4") (pintype "passive"))
    )
    (net (code "138") (name "Net-(LED94-DOUT)") (class "Default")
      (node (ref "LED94") (pin "2") (pinfunction "DOUT_2") (pintype "passive"))
      (node (ref "LED95") (pin "4") (pinfunction "DIN_4") (pintype "passive"))
    )
    (net (code "139") (name "Net-(LED95-DOUT)") (class "Default")
      (node (ref "LED95") (pin "2") (pinfunction "DOUT_2") (pintype "passive"))
      (node (ref "LED96") (pin "4") (pinfunction "DIN_4") (pintype "passive"))
    )
    (net (code "140") (name "Net-(LED96-DOUT)") (class "Default")
      (node (ref "LED96") (pin "2") (pinfunction "DOUT_2") (pintype "passive"))
      (node (ref "LED97") (pin "4") (pinfunction "DIN_4") (pintype "passive"))
    )
    (net (code "141") (name "Net-(LED97-DOUT)") (class "Default")
      (node (ref "LED97") (pin "2") (pinfunction "DOUT_2") (pintype "passive"))
      (node (ref "LED98") (pin "4") (pinfunction "DIN_4") (pintype "passive"))
    )
    (net (code "142") (name "Net-(LED98-DOUT)") (class "Default")
      (node (ref "LED98") (pin "2") (pinfunction "DOUT_2") (pintype "passive"))
      (node (ref "LED99") (pin "4") (pinfunction "DIN_4") (pintype "passive"))
    )
    (net (code "143") (name "Net-(LED100-DIN)") (class "Default")
      (node (ref "LED100") (pin "4") (pinfunction "DIN_4") (pintype "passive"))
      (node (ref "LED99") (pin "2") (pinfunction "DOUT_2") (pintype "passive"))
    )
    (net (code "144") (name "Net-(LED100-DOUT)") (class "Default")
      (node (ref "LED100") (pin "2") (pinfunction "DOUT_2") (pintype "passive"))
      (node (ref "LED101") (pin "4") (pinfunction "DIN_4") (pintype "passive"))
    )
    (net (code "145") (name "Net-(LED101-DOUT)") (class "Default")
      (node (ref "LED101") (pin "2") (pinfunction "DOUT_2") (pintype "passive"))
      (node (ref "LED102") (pin "4") (pinfunction "DIN_4") (pintype "passive"))
    )
    (net (code "146") (name "Net-(LED102-DOUT)") (class "Default")
      (node (ref "LED102") (pin "2") (pinfunction "DOUT_2") (pintype "passive"))
      (node (ref "LED103") (pin "4") (pinfunction "DIN_4") (pintype "passive"))
    )
    (net (code "147") (name "Net-(LED103-DOUT)") (class "Default")
      (node (ref "LED103") (pin "2") (pinfunction "DOUT_2") (pintype "passive"))
      (node (ref "LED104") (pin "4") (pinfunction "DIN_4") (pintype "passive"))
    )
    (net (code "148") (name "Net-(LED104-DOUT)") (class "Default")
      (node (ref "LED104") (pin "2") (pinfunction "DOUT_2") (pintype "passive"))
      (node (ref "LED105") (pin "4") (pinfunction "DIN_4") (pintype "passive"))
    )
    (net (code "149") (name "Net-(LED105-DOUT)") (class "Default")
      (node (ref "LED105") (pin "2") (pinfunction "DOUT_2") (pintype "passive"))
      (node (ref "LED106") (pin "4") (pinfunction "DIN_4") (pintype "passive"))
    )
    (net (code "150") (name "Net-(LED106-DOUT)") (class "Default")
      (node (ref "LED106") (pin "2") (pinfunction "DOUT_2") (pintype "passive"))
      (node (ref "LED107") (pin "4") (pinfunction "DIN_4") (pintype "passive"))
    )
    (net (code "151") (name "Net-(LED107-DOUT)") (class "Default")
      (node (ref "LED107") (pin "2") (pinfunction "DOUT_2") (pintype "passive"))
      (node (ref "LED108") (pin "4") (pinfunction "DIN_4") (pintype "passive"))
    )
    (net (code "152") (name "Net-(LED108-DOUT)") (class "Default")
      (node (ref "LED108") (pin "2") (pinfunction "DOUT_2") (pintype "passive"))
      (node (ref "LED109") (pin "4") (pinfunction "DIN_4") (pintype "passive"))
    )
    (net (code "153") (name "Net-(LED109-DOUT)") (class "Default")
      (node (ref "LED109") (pin "2") (pinfunction "DOUT_2") (pintype "passive"))
      (node (ref "LED110") (pin "4") (pinfunction "DIN_4") (pintype "passive"))
    )
    (net (code "154") (name "Net-(LED110-DOUT)") (class "Default")
      (node (ref "LED110") (pin "2") (pinfunction "DOUT_2") (pintype "passive"))
      (node (ref "LED111") (pin "4") (pinfunction "DIN_4") (pintype "passive"))
    )
    (net (code "155") (name "Net-(LED111-DOUT)") (class "Default")
      (node (ref "LED111") (pin "2") (pinfunction "DOUT_2") (pintype "passive"))
      (node (ref "LED112") (pin "4") (pinfunction "DIN_4") (pintype "passive"))
    )
    (net (code "156") (name "Net-(P_ON-Pad1)") (class "Default")
      (node (ref "P_ON") (pin "1") (pinfunction "1_1") (pintype "passive"))
      (node (ref "R6") (pin "2") (pinfunction "2_2") (pintype "passive"))
    )
    (net (code "157") (name "Net-(Relay1-COM)") (class "Default")
      (node (ref "Relay1") (pin "3") (pinfunction "COM_3") (pintype "passive"))
      (node (ref "esp1") (pin "35") (pinfunction "5V_35") (pintype "power_in"))
    )
    (net (code "158") (name "Net-(Screen-LED)") (class "Default")
      (node (ref "R9") (pin "1") (pinfunction "1_1") (pintype "passive"))
      (node (ref "Screen") (pin "8") (pinfunction "LED_8") (pintype "passive"))
    )
    (net (code "159") (name "Net-(Screen-VCC)") (class "Default")
      (node (ref "R8") (pin "1") (pinfunction "1_1") (pintype "passive"))
      (node (ref "Screen") (pin "1") (pinfunction "VCC_1") (pintype "passive"))
    )
    (net (code "160") (name "Net-(cp1-D+)") (class "Default")
      (node (ref "D9") (pin "2") (pinfunction "2_2") (pintype "passive"))
      (node (ref "cp1") (pin "4") (pinfunction "D+_4") (pintype "passive"))
      (node (ref "usb1") (pin "2") (pinfunction "DATA+_2") (pintype "bidirectional"))
    )
    (net (code "161") (name "Net-(cp1-D-)") (class "Default")
      (node (ref "D9") (pin "3") (pinfunction "3_3") (pintype "passive"))
      (node (ref "cp1") (pin "5") (pinfunction "D-_5") (pintype "passive"))
      (node (ref "usb1") (pin "3") (pinfunction "DATA-_3") (pintype "bidirectional"))
    )
    (net (code "162") (name "Net-(cp1-RSTb)") (class "Default")
      (node (ref "R5") (pin "2") (pinfunction "2_2") (pintype "passive"))
      (node (ref "cp1") (pin "9") (pinfunction "RSTb_9") (pintype "passive"))
    )
    (net (code "163") (name "Net-(cp1-VBUS)") (class "Default")
      (node (ref "223R") (pin "1") (pinfunction "1_1") (pintype "passive"))
      (node (ref "473R") (pin "2") (pinfunction "2_2") (pintype "passive"))
      (node (ref "cp1") (pin "8") (pinfunction "VBUS_8") (pintype "passive"))
    )
    (net (code "164") (name "USB_5V") (class "Default")
      (node (ref "223R") (pin "2") (pinfunction "2_2") (pintype "passive"))
      (node (ref "C64") (pin "2") (pinfunction "+_2") (pintype "passive"))
      (node (ref "C65") (pin "2") (pinfunction "+_2") (pintype "passive"))
      (node (ref "D9") (pin "4") (pinfunction "4_4") (pintype "passive"))
      (node (ref "Relay1") (pin "5") (pinfunction "NC_5") (pintype "passive"))
      (node (ref "cp1") (pin "7") (pinfunction "VREGIN_7") (pintype "passive"))
      (node (ref "usb1") (pin "4") (pinfunction "5V_4") (pintype "power_in"))
    )
    (net (code "165") (name "unconnected-(J2-NC-Pad5)") (class "Default")
      (node (ref "J2") (pin "5") (pinfunction "NC_5") (pintype "passive"))
    )
    (net (code "166") (name "unconnected-(cp1-CHR0-Pad15)") (class "Default")
      (node (ref "cp1") (pin "15") (pinfunction "CHR0_15") (pintype "passive"))
    )
    (net (code "167") (name "unconnected-(cp1-CHR1-Pad14)") (class "Default")
      (node (ref "cp1") (pin "14") (pinfunction "CHR1_14") (pintype "passive"))
    )
    (net (code "168") (name "unconnected-(cp1-CHREN-Pad13)") (class "Default")
      (node (ref "cp1") (pin "13") (pinfunction "CHREN_13") (pintype "passive"))
    )
    (net (code "169") (name "unconnected-(cp1-CTS49-Pad23)") (class "Default")
      (node (ref "cp1") (pin "23") (pinfunction "CTS49_23") (pintype "passive"))
    )
    (net (code "170") (name "unconnected-(cp1-DCD-Pad1)") (class "Default")
      (node (ref "cp1") (pin "1") (pinfunction "DCD_1") (pintype "passive"))
    )
    (net (code "171") (name "unconnected-(cp1-DSR-Pad27)") (class "Default")
      (node (ref "cp1") (pin "27") (pinfunction "DSR_27") (pintype "passive"))
    )
    (net (code "172") (name "unconnected-(cp1-IO0{slash}TXT-Pad19)") (class "Default")
      (node (ref "cp1") (pin "19") (pinfunction "IO0/TXT_19") (pintype "passive"))
    )
    (net (code "173") (name "unconnected-(cp1-IO1{slash}RXT-Pad18)") (class "Default")
      (node (ref "cp1") (pin "18") (pinfunction "IO1/RXT_18") (pintype "passive"))
    )
    (net (code "174") (name "unconnected-(cp1-IO2{slash}RS485-Pad17)") (class "Default")
      (node (ref "cp1") (pin "17") (pinfunction "IO2/RS485_17") (pintype "passive"))
    )
    (net (code "175") (name "unconnected-(cp1-IO3{slash}wakeup-Pad16)") (class "Default")
      (node (ref "cp1") (pin "16") (pinfunction "IO3/wakeup_16") (pintype "passive"))
    )
    (net (code "176") (name "unconnected-(cp1-IO4-Pad22)") (class "Default")
      (node (ref "cp1") (pin "22") (pinfunction "IO4_22") (pintype "passive"))
    )
    (net (code "177") (name "unconnected-(cp1-IO5-Pad21)") (class "Default")
      (node (ref "cp1") (pin "21") (pinfunction "IO5_21") (pintype "passive"))
    )
    (net (code "178") (name "unconnected-(cp1-IO6-Pad20)") (class "Default")
      (node (ref "cp1") (pin "20") (pinfunction "IO6_20") (pintype "passive"))
    )
    (net (code "179") (name "unconnected-(cp1-NC-Pad10)") (class "Default")
      (node (ref "cp1") (pin "10") (pinfunction "NC_10") (pintype "passive"))
    )
    (net (code "180") (name "unconnected-(cp1-RI{slash}CLK-Pad2)") (class "Default")
      (node (ref "cp1") (pin "2") (pinfunction "RI/CLK_2") (pintype "passive"))
    )
    (net (code "181") (name "unconnected-(cp1-SUS-Pad12)") (class "Default")
      (node (ref "cp1") (pin "12") (pinfunction "SUS_12") (pintype "passive"))
    )
    (net (code "182") (name "unconnected-(cp1-SUSb-Pad11)") (class "Default")
      (node (ref "cp1") (pin "11") (pinfunction "SUSb_11") (pintype "passive"))
    )
    (net (code "183") (name "unconnected-(esp1-3v3-Pad21)") (class "Default")
      (node (ref "esp1") (pin "21") (pinfunction "3v3_21") (pintype "power_in"))
    )
    (net (code "184") (name "unconnected-(esp1-5V-Pad13)") (class "Default")
      (node (ref "esp1") (pin "13") (pinfunction "5V_13") (pintype "power_in"))
    )
  )
)
